# axiom_beta_interface_dummy_v0_13_r1_3.net
KiCad netlist of a schematic drawn in EAGLE
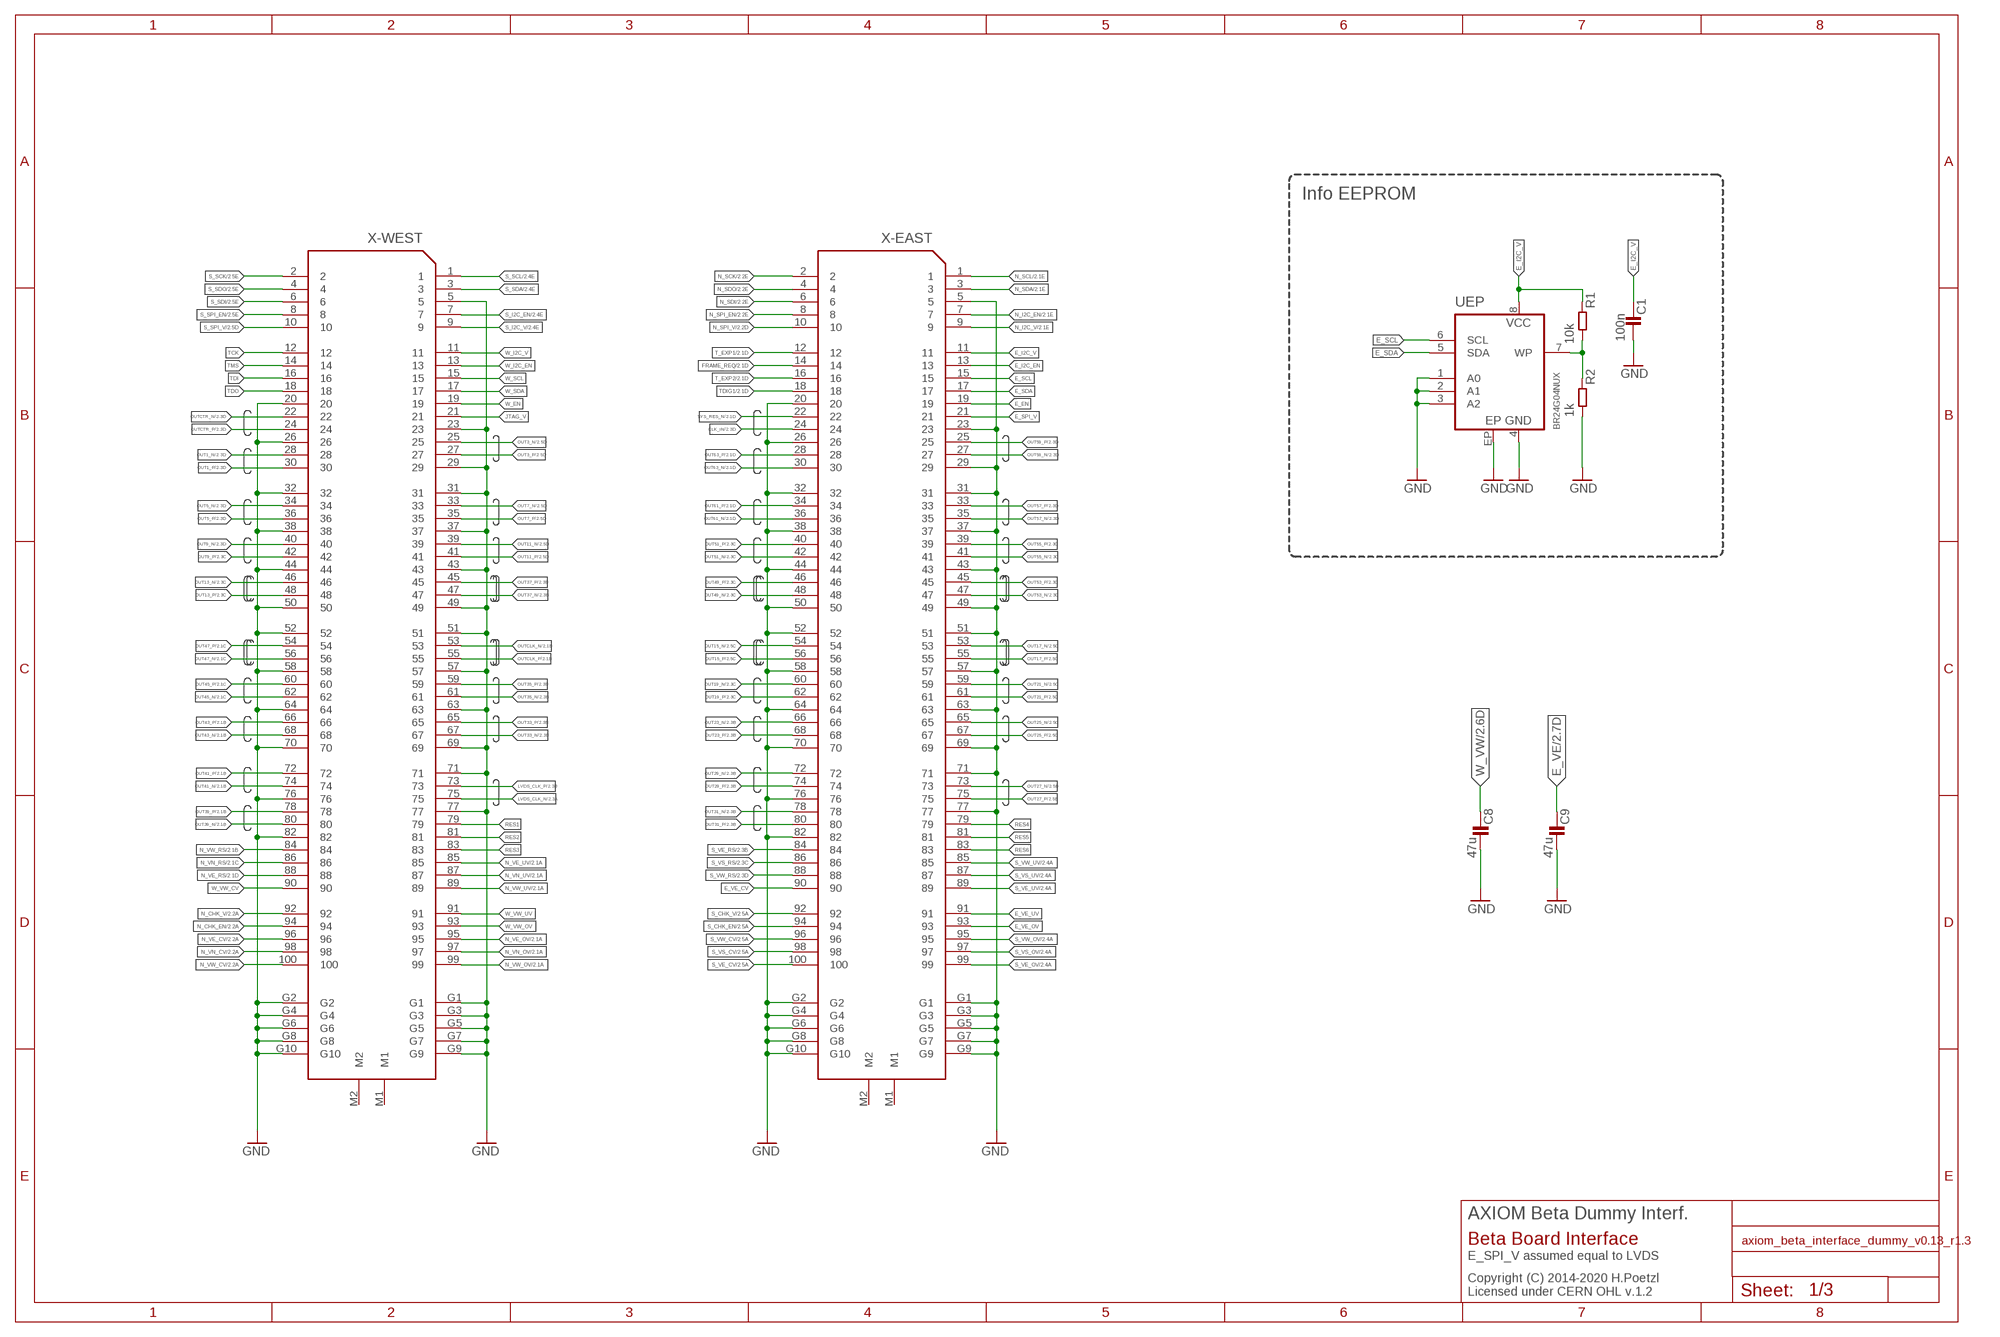
[diagram p0: schematic, sheet 1]
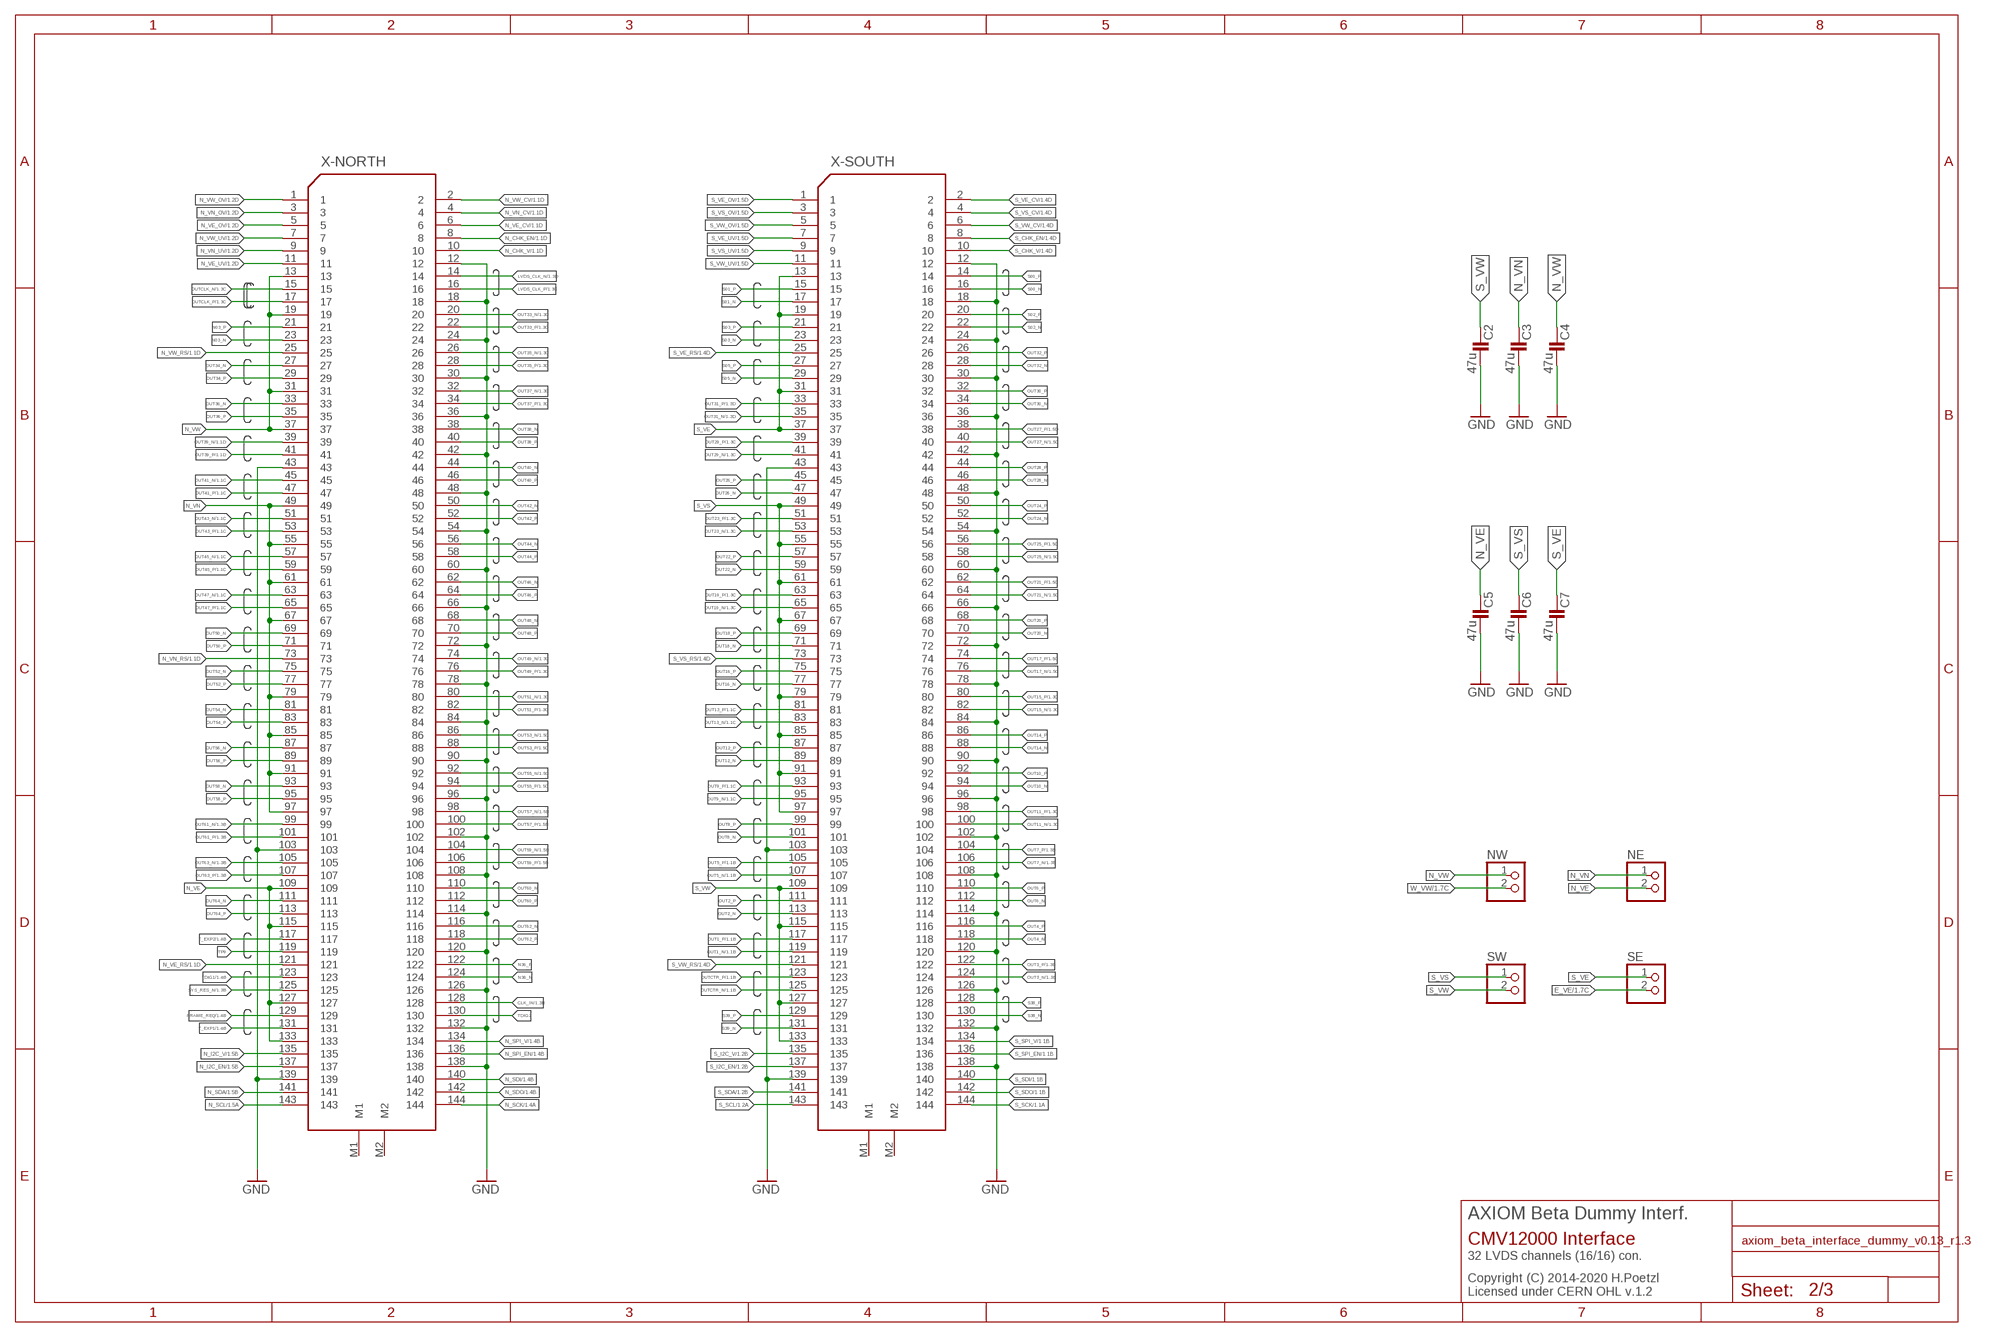
[diagram p1: schematic, sheet 2]
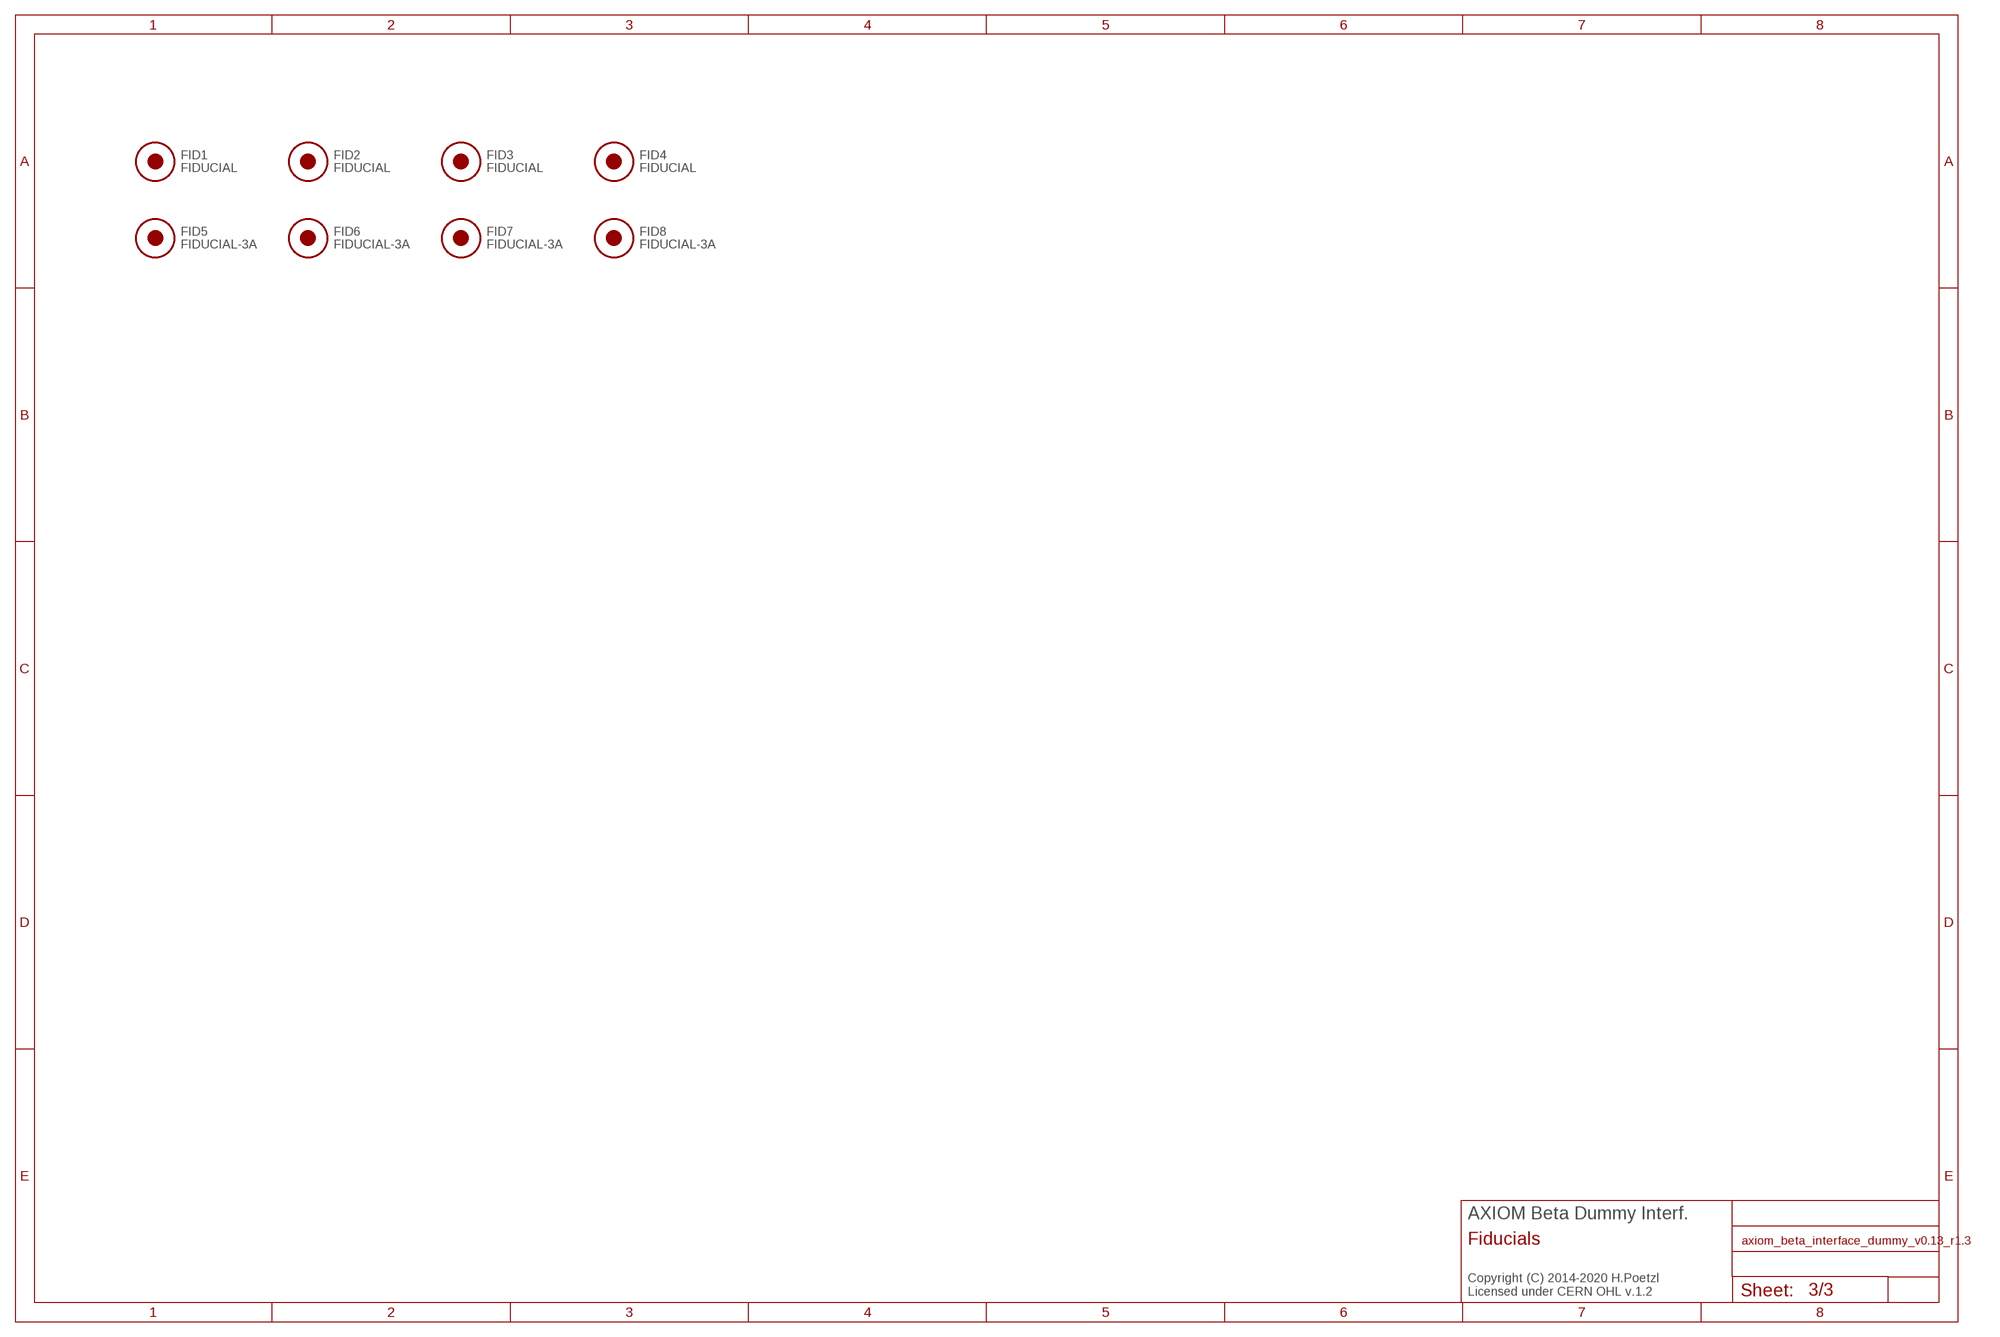
[diagram p2: schematic, sheet 3]

(export (version "E")
  (design (tool "Eeschema 10.0.6"))
  (components
    (comp (ref "C1")
      (value "100n")
      (footprint "eagle-import:0402-B")
      (libsource (lib "eagle-import") (part "C0402-B"))
    )
    (comp (ref "C8")
      (value "47u")
      (footprint "eagle-import:0805-B")
      (libsource (lib "eagle-import") (part "C0805-B"))
    )
    (comp (ref "C9")
      (value "47u")
      (footprint "eagle-import:0805-B")
      (libsource (lib "eagle-import") (part "C0805-B"))
    )
    (comp (ref "R1")
      (value "10k")
      (footprint "eagle-import:0402-B")
      (libsource (lib "eagle-import") (part "R0402-B"))
    )
    (comp (ref "R2")
      (value "1k")
      (footprint "eagle-import:0402-B")
      (libsource (lib "eagle-import") (part "R0402-B"))
    )
    (comp (ref "UEP")
      (value "BR24G04NUX")
      (footprint "eagle-import:DFN200X300X100-9N")
      (libsource (lib "eagle-import") (part "BR24G04NUX"))
    )
    (comp (ref "X-EAST")
      (value "FX10-100/10P")
      (footprint "eagle-import:FX10A-100P_10")
      (libsource (lib "eagle-import") (part "FX10-100/10P"))
    )
    (comp (ref "X-WEST")
      (value "FX10-100/10P")
      (footprint "eagle-import:FX10A-100P_10")
      (libsource (lib "eagle-import") (part "FX10-100/10P"))
    )
    (comp (ref "FID1")
      (value "FIDUCIAL")
      (footprint "eagle-import:FID_ARROW")
      (libsource (lib "eagle-import") (part "FIDUCIAL"))
    )
    (comp (ref "FID2")
      (value "FIDUCIAL")
      (footprint "eagle-import:FID_ARROW")
      (libsource (lib "eagle-import") (part "FIDUCIAL"))
    )
    (comp (ref "FID3")
      (value "FIDUCIAL")
      (footprint "eagle-import:FID_ARROW")
      (libsource (lib "eagle-import") (part "FIDUCIAL"))
    )
    (comp (ref "FID4")
      (value "FIDUCIAL")
      (footprint "eagle-import:FID_ARROW")
      (libsource (lib "eagle-import") (part "FIDUCIAL"))
    )
    (comp (ref "FID5")
      (value "FIDUCIAL-3A")
      (footprint "eagle-import:FID_3ARROW")
      (libsource (lib "eagle-import") (part "FIDUCIAL-3A"))
    )
    (comp (ref "FID6")
      (value "FIDUCIAL-3A")
      (footprint "eagle-import:FID_3ARROW")
      (libsource (lib "eagle-import") (part "FIDUCIAL-3A"))
    )
    (comp (ref "FID7")
      (value "FIDUCIAL-3A")
      (footprint "eagle-import:FID_3ARROW")
      (libsource (lib "eagle-import") (part "FIDUCIAL-3A"))
    )
    (comp (ref "FID8")
      (value "FIDUCIAL-3A")
      (footprint "eagle-import:FID_3ARROW")
      (libsource (lib "eagle-import") (part "FIDUCIAL-3A"))
    )
    (comp (ref "C2")
      (value "47u")
      (footprint "eagle-import:0805-B")
      (libsource (lib "eagle-import") (part "C0805-B"))
    )
    (comp (ref "C3")
      (value "47u")
      (footprint "eagle-import:0805-B")
      (libsource (lib "eagle-import") (part "C0805-B"))
    )
    (comp (ref "C4")
      (value "47u")
      (footprint "eagle-import:0805-B")
      (libsource (lib "eagle-import") (part "C0805-B"))
    )
    (comp (ref "C5")
      (value "47u")
      (footprint "eagle-import:0805-B")
      (libsource (lib "eagle-import") (part "C0805-B"))
    )
    (comp (ref "C6")
      (value "47u")
      (footprint "eagle-import:0805-B")
      (libsource (lib "eagle-import") (part "C0805-B"))
    )
    (comp (ref "C7")
      (value "47u")
      (footprint "eagle-import:0805-B")
      (libsource (lib "eagle-import") (part "C0805-B"))
    )
    (comp (ref "NE")
      (value "PINHD-1X02_2.54")
      (footprint "eagle-import:1X02")
      (libsource (lib "eagle-import") (part "PINHD-1X02_2.54"))
    )
    (comp (ref "NW")
      (value "PINHD-1X02_2.54")
      (footprint "eagle-import:1X02")
      (libsource (lib "eagle-import") (part "PINHD-1X02_2.54"))
    )
    (comp (ref "SE")
      (value "PINHD-1X02_2.54")
      (footprint "eagle-import:1X02")
      (libsource (lib "eagle-import") (part "PINHD-1X02_2.54"))
    )
    (comp (ref "SW")
      (value "PINHD-1X02_2.54")
      (footprint "eagle-import:1X02")
      (libsource (lib "eagle-import") (part "PINHD-1X02_2.54"))
    )
    (comp (ref "X-NORTH")
      (value "FX10-144S")
      (footprint "eagle-import:FX10A-144S")
      (libsource (lib "eagle-import") (part "FX10-144S"))
    )
    (comp (ref "X-SOUTH")
      (value "FX10-144S")
      (footprint "eagle-import:FX10A-144S")
      (libsource (lib "eagle-import") (part "FX10-144S"))
    )
  )
  (nets
    (net (code "1") (name "CLK_IN") (class "Default")
      (node (ref "X-EAST") (pin "24") (pinfunction "24_24") (pintype "bidirectional"))
      (node (ref "X-NORTH") (pin "128") (pinfunction "128_128") (pintype "bidirectional"))
    )
    (net (code "2") (name "E_EN") (class "Default")
      (node (ref "X-EAST") (pin "19") (pinfunction "19_19") (pintype "bidirectional"))
    )
    (net (code "3") (name "E_I2C_EN") (class "Default")
      (node (ref "X-EAST") (pin "13") (pinfunction "13_13") (pintype "bidirectional"))
    )
    (net (code "4") (name "E_I2C_V") (class "Default")
      (node (ref "C1") (pin "1") (pinfunction "1_1") (pintype "passive"))
      (node (ref "R1") (pin "1") (pinfunction "1_1") (pintype "passive"))
      (node (ref "UEP") (pin "8") (pinfunction "VCC_8") (pintype "power_in"))
      (node (ref "X-EAST") (pin "11") (pinfunction "11_11") (pintype "bidirectional"))
    )
    (net (code "5") (name "E_SCL") (class "Default")
      (node (ref "UEP") (pin "6") (pinfunction "SCL_6") (pintype "input"))
      (node (ref "X-EAST") (pin "15") (pinfunction "15_15") (pintype "bidirectional"))
    )
    (net (code "6") (name "E_SDA") (class "Default")
      (node (ref "UEP") (pin "5") (pinfunction "SDA_5") (pintype "bidirectional"))
      (node (ref "X-EAST") (pin "17") (pinfunction "17_17") (pintype "bidirectional"))
    )
    (net (code "7") (name "E_SPI_V") (class "Default")
      (node (ref "X-EAST") (pin "21") (pinfunction "21_21") (pintype "bidirectional"))
    )
    (net (code "8") (name "E_VE") (class "Default")
      (node (ref "C9") (pin "1") (pinfunction "1_1") (pintype "passive"))
      (node (ref "SE") (pin "2") (pinfunction "2_2") (pintype "passive"))
    )
    (net (code "9") (name "E_VE_CV") (class "Default")
      (node (ref "X-EAST") (pin "90") (pinfunction "90_90") (pintype "bidirectional"))
    )
    (net (code "10") (name "E_VE_OV") (class "Default")
      (node (ref "X-EAST") (pin "93") (pinfunction "93_93") (pintype "bidirectional"))
    )
    (net (code "11") (name "E_VE_UV") (class "Default")
      (node (ref "X-EAST") (pin "91") (pinfunction "91_91") (pintype "bidirectional"))
    )
    (net (code "12") (name "FRAME_REQ") (class "Default")
      (node (ref "X-EAST") (pin "14") (pinfunction "14_14") (pintype "bidirectional"))
      (node (ref "X-NORTH") (pin "129") (pinfunction "129_129") (pintype "bidirectional"))
    )
    (net (code "13") (name "GND") (class "Default")
      (node (ref "C1") (pin "2") (pinfunction "2_2") (pintype "passive"))
      (node (ref "C2") (pin "2") (pinfunction "2_2") (pintype "passive"))
      (node (ref "C3") (pin "2") (pinfunction "2_2") (pintype "passive"))
      (node (ref "C4") (pin "2") (pinfunction "2_2") (pintype "passive"))
      (node (ref "C5") (pin "2") (pinfunction "2_2") (pintype "passive"))
      (node (ref "C6") (pin "2") (pinfunction "2_2") (pintype "passive"))
      (node (ref "C7") (pin "2") (pinfunction "2_2") (pintype "passive"))
      (node (ref "C8") (pin "2") (pinfunction "2_2") (pintype "passive"))
      (node (ref "C9") (pin "2") (pinfunction "2_2") (pintype "passive"))
      (node (ref "R2") (pin "2") (pinfunction "2_2") (pintype "passive"))
      (node (ref "UEP") (pin "1") (pinfunction "A0_1") (pintype "input"))
      (node (ref "UEP") (pin "2") (pinfunction "A1_2") (pintype "input"))
      (node (ref "UEP") (pin "3") (pinfunction "A2_3") (pintype "input"))
      (node (ref "UEP") (pin "4") (pinfunction "GND_4") (pintype "passive"))
      (node (ref "UEP") (pin "EP") (pinfunction "EP_EP") (pintype "passive"))
      (node (ref "X-EAST") (pin "20") (pinfunction "20_20") (pintype "bidirectional"))
      (node (ref "X-EAST") (pin "23") (pinfunction "23_23") (pintype "bidirectional"))
      (node (ref "X-EAST") (pin "26") (pinfunction "26_26") (pintype "bidirectional"))
      (node (ref "X-EAST") (pin "29") (pinfunction "29_29") (pintype "bidirectional"))
      (node (ref "X-EAST") (pin "31") (pinfunction "31_31") (pintype "bidirectional"))
      (node (ref "X-EAST") (pin "32") (pinfunction "32_32") (pintype "bidirectional"))
      (node (ref "X-EAST") (pin "37") (pinfunction "37_37") (pintype "bidirectional"))
      (node (ref "X-EAST") (pin "38") (pinfunction "38_38") (pintype "bidirectional"))
      (node (ref "X-EAST") (pin "43") (pinfunction "43_43") (pintype "bidirectional"))
      (node (ref "X-EAST") (pin "44") (pinfunction "44_44") (pintype "bidirectional"))
      (node (ref "X-EAST") (pin "49") (pinfunction "49_49") (pintype "bidirectional"))
      (node (ref "X-EAST") (pin "5") (pinfunction "5_5") (pintype "bidirectional"))
      (node (ref "X-EAST") (pin "50") (pinfunction "50_50") (pintype "bidirectional"))
      (node (ref "X-EAST") (pin "51") (pinfunction "51_51") (pintype "bidirectional"))
      (node (ref "X-EAST") (pin "52") (pinfunction "52_52") (pintype "bidirectional"))
      (node (ref "X-EAST") (pin "57") (pinfunction "57_57") (pintype "bidirectional"))
      (node (ref "X-EAST") (pin "58") (pinfunction "58_58") (pintype "bidirectional"))
      (node (ref "X-EAST") (pin "63") (pinfunction "63_63") (pintype "bidirectional"))
      (node (ref "X-EAST") (pin "64") (pinfunction "64_64") (pintype "bidirectional"))
      (node (ref "X-EAST") (pin "69") (pinfunction "69_69") (pintype "bidirectional"))
      (node (ref "X-EAST") (pin "70") (pinfunction "70_70") (pintype "bidirectional"))
      (node (ref "X-EAST") (pin "71") (pinfunction "71_71") (pintype "bidirectional"))
      (node (ref "X-EAST") (pin "76") (pinfunction "76_76") (pintype "bidirectional"))
      (node (ref "X-EAST") (pin "77") (pinfunction "77_77") (pintype "bidirectional"))
      (node (ref "X-EAST") (pin "82") (pinfunction "82_82") (pintype "bidirectional"))
      (node (ref "X-EAST") (pin "G1") (pinfunction "G1_G1") (pintype "bidirectional"))
      (node (ref "X-EAST") (pin "G10") (pinfunction "G10_G10") (pintype "bidirectional"))
      (node (ref "X-EAST") (pin "G2") (pinfunction "G2_G2") (pintype "bidirectional"))
      (node (ref "X-EAST") (pin "G3") (pinfunction "G3_G3") (pintype "bidirectional"))
      (node (ref "X-EAST") (pin "G4") (pinfunction "G4_G4") (pintype "bidirectional"))
      (node (ref "X-EAST") (pin "G5") (pinfunction "G5_G5") (pintype "bidirectional"))
      (node (ref "X-EAST") (pin "G6") (pinfunction "G6_G6") (pintype "bidirectional"))
      (node (ref "X-EAST") (pin "G7") (pinfunction "G7_G7") (pintype "bidirectional"))
      (node (ref "X-EAST") (pin "G8") (pinfunction "G8_G8") (pintype "bidirectional"))
      (node (ref "X-EAST") (pin "G9") (pinfunction "G9_G9") (pintype "bidirectional"))
      (node (ref "X-NORTH") (pin "102") (pinfunction "102_102") (pintype "bidirectional"))
      (node (ref "X-NORTH") (pin "103") (pinfunction "103_103") (pintype "bidirectional"))
      (node (ref "X-NORTH") (pin "108") (pinfunction "108_108") (pintype "bidirectional"))
      (node (ref "X-NORTH") (pin "114") (pinfunction "114_114") (pintype "bidirectional"))
      (node (ref "X-NORTH") (pin "12") (pinfunction "12_12") (pintype "bidirectional"))
      (node (ref "X-NORTH") (pin "120") (pinfunction "120_120") (pintype "bidirectional"))
      (node (ref "X-NORTH") (pin "126") (pinfunction "126_126") (pintype "bidirectional"))
      (node (ref "X-NORTH") (pin "132") (pinfunction "132_132") (pintype "bidirectional"))
      (node (ref "X-NORTH") (pin "138") (pinfunction "138_138") (pintype "bidirectional"))
      (node (ref "X-NORTH") (pin "139") (pinfunction "139_139") (pintype "bidirectional"))
      (node (ref "X-NORTH") (pin "18") (pinfunction "18_18") (pintype "bidirectional"))
      (node (ref "X-NORTH") (pin "24") (pinfunction "24_24") (pintype "bidirectional"))
      (node (ref "X-NORTH") (pin "30") (pinfunction "30_30") (pintype "bidirectional"))
      (node (ref "X-NORTH") (pin "36") (pinfunction "36_36") (pintype "bidirectional"))
      (node (ref "X-NORTH") (pin "42") (pinfunction "42_42") (pintype "bidirectional"))
      (node (ref "X-NORTH") (pin "43") (pinfunction "43_43") (pintype "bidirectional"))
      (node (ref "X-NORTH") (pin "48") (pinfunction "48_48") (pintype "bidirectional"))
      (node (ref "X-NORTH") (pin "54") (pinfunction "54_54") (pintype "bidirectional"))
      (node (ref "X-NORTH") (pin "60") (pinfunction "60_60") (pintype "bidirectional"))
      (node (ref "X-NORTH") (pin "66") (pinfunction "66_66") (pintype "bidirectional"))
      (node (ref "X-NORTH") (pin "72") (pinfunction "72_72") (pintype "bidirectional"))
      (node (ref "X-NORTH") (pin "78") (pinfunction "78_78") (pintype "bidirectional"))
      (node (ref "X-NORTH") (pin "84") (pinfunction "84_84") (pintype "bidirectional"))
      (node (ref "X-NORTH") (pin "90") (pinfunction "90_90") (pintype "bidirectional"))
      (node (ref "X-NORTH") (pin "96") (pinfunction "96_96") (pintype "bidirectional"))
      (node (ref "X-SOUTH") (pin "102") (pinfunction "102_102") (pintype "bidirectional"))
      (node (ref "X-SOUTH") (pin "103") (pinfunction "103_103") (pintype "bidirectional"))
      (node (ref "X-SOUTH") (pin "108") (pinfunction "108_108") (pintype "bidirectional"))
      (node (ref "X-SOUTH") (pin "114") (pinfunction "114_114") (pintype "bidirectional"))
      (node (ref "X-SOUTH") (pin "12") (pinfunction "12_12") (pintype "bidirectional"))
      (node (ref "X-SOUTH") (pin "120") (pinfunction "120_120") (pintype "bidirectional"))
      (node (ref "X-SOUTH") (pin "126") (pinfunction "126_126") (pintype "bidirectional"))
      (node (ref "X-SOUTH") (pin "132") (pinfunction "132_132") (pintype "bidirectional"))
      (node (ref "X-SOUTH") (pin "138") (pinfunction "138_138") (pintype "bidirectional"))
      (node (ref "X-SOUTH") (pin "139") (pinfunction "139_139") (pintype "bidirectional"))
      (node (ref "X-SOUTH") (pin "18") (pinfunction "18_18") (pintype "bidirectional"))
      (node (ref "X-SOUTH") (pin "24") (pinfunction "24_24") (pintype "bidirectional"))
      (node (ref "X-SOUTH") (pin "30") (pinfunction "30_30") (pintype "bidirectional"))
      (node (ref "X-SOUTH") (pin "36") (pinfunction "36_36") (pintype "bidirectional"))
      (node (ref "X-SOUTH") (pin "42") (pinfunction "42_42") (pintype "bidirectional"))
      (node (ref "X-SOUTH") (pin "43") (pinfunction "43_43") (pintype "bidirectional"))
      (node (ref "X-SOUTH") (pin "48") (pinfunction "48_48") (pintype "bidirectional"))
      (node (ref "X-SOUTH") (pin "54") (pinfunction "54_54") (pintype "bidirectional"))
      (node (ref "X-SOUTH") (pin "60") (pinfunction "60_60") (pintype "bidirectional"))
      (node (ref "X-SOUTH") (pin "66") (pinfunction "66_66") (pintype "bidirectional"))
      (node (ref "X-SOUTH") (pin "72") (pinfunction "72_72") (pintype "bidirectional"))
      (node (ref "X-SOUTH") (pin "78") (pinfunction "78_78") (pintype "bidirectional"))
      (node (ref "X-SOUTH") (pin "84") (pinfunction "84_84") (pintype "bidirectional"))
      (node (ref "X-SOUTH") (pin "90") (pinfunction "90_90") (pintype "bidirectional"))
      (node (ref "X-SOUTH") (pin "96") (pinfunction "96_96") (pintype "bidirectional"))
      (node (ref "X-WEST") (pin "20") (pinfunction "20_20") (pintype "bidirectional"))
      (node (ref "X-WEST") (pin "23") (pinfunction "23_23") (pintype "bidirectional"))
      (node (ref "X-WEST") (pin "26") (pinfunction "26_26") (pintype "bidirectional"))
      (node (ref "X-WEST") (pin "29") (pinfunction "29_29") (pintype "bidirectional"))
      (node (ref "X-WEST") (pin "31") (pinfunction "31_31") (pintype "bidirectional"))
      (node (ref "X-WEST") (pin "32") (pinfunction "32_32") (pintype "bidirectional"))
      (node (ref "X-WEST") (pin "37") (pinfunction "37_37") (pintype "bidirectional"))
      (node (ref "X-WEST") (pin "38") (pinfunction "38_38") (pintype "bidirectional"))
      (node (ref "X-WEST") (pin "43") (pinfunction "43_43") (pintype "bidirectional"))
      (node (ref "X-WEST") (pin "44") (pinfunction "44_44") (pintype "bidirectional"))
      (node (ref "X-WEST") (pin "49") (pinfunction "49_49") (pintype "bidirectional"))
      (node (ref "X-WEST") (pin "5") (pinfunction "5_5") (pintype "bidirectional"))
      (node (ref "X-WEST") (pin "50") (pinfunction "50_50") (pintype "bidirectional"))
      (node (ref "X-WEST") (pin "51") (pinfunction "51_51") (pintype "bidirectional"))
      (node (ref "X-WEST") (pin "52") (pinfunction "52_52") (pintype "bidirectional"))
      (node (ref "X-WEST") (pin "57") (pinfunction "57_57") (pintype "bidirectional"))
      (node (ref "X-WEST") (pin "58") (pinfunction "58_58") (pintype "bidirectional"))
      (node (ref "X-WEST") (pin "63") (pinfunction "63_63") (pintype "bidirectional"))
      (node (ref "X-WEST") (pin "64") (pinfunction "64_64") (pintype "bidirectional"))
      (node (ref "X-WEST") (pin "69") (pinfunction "69_69") (pintype "bidirectional"))
      (node (ref "X-WEST") (pin "70") (pinfunction "70_70") (pintype "bidirectional"))
      (node (ref "X-WEST") (pin "71") (pinfunction "71_71") (pintype "bidirectional"))
      (node (ref "X-WEST") (pin "76") (pinfunction "76_76") (pintype "bidirectional"))
      (node (ref "X-WEST") (pin "77") (pinfunction "77_77") (pintype "bidirectional"))
      (node (ref "X-WEST") (pin "82") (pinfunction "82_82") (pintype "bidirectional"))
      (node (ref "X-WEST") (pin "G1") (pinfunction "G1_G1") (pintype "bidirectional"))
      (node (ref "X-WEST") (pin "G10") (pinfunction "G10_G10") (pintype "bidirectional"))
      (node (ref "X-WEST") (pin "G2") (pinfunction "G2_G2") (pintype "bidirectional"))
      (node (ref "X-WEST") (pin "G3") (pinfunction "G3_G3") (pintype "bidirectional"))
      (node (ref "X-WEST") (pin "G4") (pinfunction "G4_G4") (pintype "bidirectional"))
      (node (ref "X-WEST") (pin "G5") (pinfunction "G5_G5") (pintype "bidirectional"))
      (node (ref "X-WEST") (pin "G6") (pinfunction "G6_G6") (pintype "bidirectional"))
      (node (ref "X-WEST") (pin "G7") (pinfunction "G7_G7") (pintype "bidirectional"))
      (node (ref "X-WEST") (pin "G8") (pinfunction "G8_G8") (pintype "bidirectional"))
      (node (ref "X-WEST") (pin "G9") (pinfunction "G9_G9") (pintype "bidirectional"))
    )
    (net (code "14") (name "JTAG_V") (class "Default")
      (node (ref "X-WEST") (pin "21") (pinfunction "21_21") (pintype "bidirectional"))
    )
    (net (code "15") (name "LVDS_CLK_N") (class "Default")
      (node (ref "X-NORTH") (pin "14") (pinfunction "14_14") (pintype "bidirectional"))
      (node (ref "X-WEST") (pin "75") (pinfunction "75_75") (pintype "bidirectional"))
    )
    (net (code "16") (name "LVDS_CLK_P") (class "Default")
      (node (ref "X-NORTH") (pin "16") (pinfunction "16_16") (pintype "bidirectional"))
      (node (ref "X-WEST") (pin "73") (pinfunction "73_73") (pintype "bidirectional"))
    )
    (net (code "17") (name "N03_N") (class "Default")
      (node (ref "X-NORTH") (pin "23") (pinfunction "23_23") (pintype "bidirectional"))
    )
    (net (code "18") (name "N03_P") (class "Default")
      (node (ref "X-NORTH") (pin "21") (pinfunction "21_21") (pintype "bidirectional"))
    )
    (net (code "19") (name "N36_N") (class "Default")
      (node (ref "X-NORTH") (pin "124") (pinfunction "124_124") (pintype "bidirectional"))
    )
    (net (code "20") (name "N36_P") (class "Default")
      (node (ref "X-NORTH") (pin "122") (pinfunction "122_122") (pintype "bidirectional"))
    )
    (net (code "21") (name "N_CHK_EN") (class "Default")
      (node (ref "X-NORTH") (pin "8") (pinfunction "8_8") (pintype "bidirectional"))
      (node (ref "X-WEST") (pin "94") (pinfunction "94_94") (pintype "bidirectional"))
    )
    (net (code "22") (name "N_CHK_V") (class "Default")
      (node (ref "X-NORTH") (pin "10") (pinfunction "10_10") (pintype "bidirectional"))
      (node (ref "X-WEST") (pin "92") (pinfunction "92_92") (pintype "bidirectional"))
    )
    (net (code "23") (name "N_I2C_EN") (class "Default")
      (node (ref "X-EAST") (pin "7") (pinfunction "7_7") (pintype "bidirectional"))
      (node (ref "X-NORTH") (pin "137") (pinfunction "137_137") (pintype "bidirectional"))
    )
    (net (code "24") (name "N_I2C_V") (class "Default")
      (node (ref "X-EAST") (pin "9") (pinfunction "9_9") (pintype "bidirectional"))
      (node (ref "X-NORTH") (pin "135") (pinfunction "135_135") (pintype "bidirectional"))
    )
    (net (code "25") (name "N_SCK") (class "Default")
      (node (ref "X-EAST") (pin "2") (pinfunction "2_2") (pintype "bidirectional"))
      (node (ref "X-NORTH") (pin "144") (pinfunction "144_144") (pintype "bidirectional"))
    )
    (net (code "26") (name "N_SCL") (class "Default")
      (node (ref "X-EAST") (pin "1") (pinfunction "1_1") (pintype "bidirectional"))
      (node (ref "X-NORTH") (pin "143") (pinfunction "143_143") (pintype "bidirectional"))
    )
    (net (code "27") (name "N_SDA") (class "Default")
      (node (ref "X-EAST") (pin "3") (pinfunction "3_3") (pintype "bidirectional"))
      (node (ref "X-NORTH") (pin "141") (pinfunction "141_141") (pintype "bidirectional"))
    )
    (net (code "28") (name "N_SDI") (class "Default")
      (node (ref "X-EAST") (pin "6") (pinfunction "6_6") (pintype "bidirectional"))
      (node (ref "X-NORTH") (pin "140") (pinfunction "140_140") (pintype "bidirectional"))
    )
    (net (code "29") (name "N_SDO") (class "Default")
      (node (ref "X-EAST") (pin "4") (pinfunction "4_4") (pintype "bidirectional"))
      (node (ref "X-NORTH") (pin "142") (pinfunction "142_142") (pintype "bidirectional"))
    )
    (net (code "30") (name "N_SPI_EN") (class "Default")
      (node (ref "X-EAST") (pin "8") (pinfunction "8_8") (pintype "bidirectional"))
      (node (ref "X-NORTH") (pin "136") (pinfunction "136_136") (pintype "bidirectional"))
    )
    (net (code "31") (name "N_SPI_V") (class "Default")
      (node (ref "X-EAST") (pin "10") (pinfunction "10_10") (pintype "bidirectional"))
      (node (ref "X-NORTH") (pin "134") (pinfunction "134_134") (pintype "bidirectional"))
    )
    (net (code "32") (name "N_VE") (class "Default")
      (node (ref "C5") (pin "1") (pinfunction "1_1") (pintype "passive"))
      (node (ref "NE") (pin "2") (pinfunction "2_2") (pintype "passive"))
      (node (ref "X-NORTH") (pin "109") (pinfunction "109_109") (pintype "bidirectional"))
      (node (ref "X-NORTH") (pin "115") (pinfunction "115_115") (pintype "bidirectional"))
      (node (ref "X-NORTH") (pin "127") (pinfunction "127_127") (pintype "bidirectional"))
      (node (ref "X-NORTH") (pin "133") (pinfunction "133_133") (pintype "bidirectional"))
    )
    (net (code "33") (name "N_VE_CV") (class "Default")
      (node (ref "X-NORTH") (pin "6") (pinfunction "6_6") (pintype "bidirectional"))
      (node (ref "X-WEST") (pin "96") (pinfunction "96_96") (pintype "bidirectional"))
    )
    (net (code "34") (name "N_VE_OV") (class "Default")
      (node (ref "X-NORTH") (pin "5") (pinfunction "5_5") (pintype "bidirectional"))
      (node (ref "X-WEST") (pin "95") (pinfunction "95_95") (pintype "bidirectional"))
    )
    (net (code "35") (name "N_VE_RS") (class "Default")
      (node (ref "X-NORTH") (pin "121") (pinfunction "121_121") (pintype "bidirectional"))
      (node (ref "X-WEST") (pin "88") (pinfunction "88_88") (pintype "bidirectional"))
    )
    (net (code "36") (name "N_VE_UV") (class "Default")
      (node (ref "X-NORTH") (pin "11") (pinfunction "11_11") (pintype "bidirectional"))
      (node (ref "X-WEST") (pin "85") (pinfunction "85_85") (pintype "bidirectional"))
    )
    (net (code "37") (name "N_VN") (class "Default")
      (node (ref "C3") (pin "1") (pinfunction "1_1") (pintype "passive"))
      (node (ref "NE") (pin "1") (pinfunction "1_1") (pintype "passive"))
      (node (ref "X-NORTH") (pin "49") (pinfunction "49_49") (pintype "bidirectional"))
      (node (ref "X-NORTH") (pin "55") (pinfunction "55_55") (pintype "bidirectional"))
      (node (ref "X-NORTH") (pin "61") (pinfunction "61_61") (pintype "bidirectional"))
      (node (ref "X-NORTH") (pin "67") (pinfunction "67_67") (pintype "bidirectional"))
      (node (ref "X-NORTH") (pin "79") (pinfunction "79_79") (pintype "bidirectional"))
      (node (ref "X-NORTH") (pin "85") (pinfunction "85_85") (pintype "bidirectional"))
      (node (ref "X-NORTH") (pin "91") (pinfunction "91_91") (pintype "bidirectional"))
      (node (ref "X-NORTH") (pin "97") (pinfunction "97_97") (pintype "bidirectional"))
    )
    (net (code "38") (name "N_VN_CV") (class "Default")
      (node (ref "X-NORTH") (pin "4") (pinfunction "4_4") (pintype "bidirectional"))
      (node (ref "X-WEST") (pin "98") (pinfunction "98_98") (pintype "bidirectional"))
    )
    (net (code "39") (name "N_VN_OV") (class "Default")
      (node (ref "X-NORTH") (pin "3") (pinfunction "3_3") (pintype "bidirectional"))
      (node (ref "X-WEST") (pin "97") (pinfunction "97_97") (pintype "bidirectional"))
    )
    (net (code "40") (name "N_VN_RS") (class "Default")
      (node (ref "X-NORTH") (pin "73") (pinfunction "73_73") (pintype "bidirectional"))
      (node (ref "X-WEST") (pin "86") (pinfunction "86_86") (pintype "bidirectional"))
    )
    (net (code "41") (name "N_VN_UV") (class "Default")
      (node (ref "X-NORTH") (pin "9") (pinfunction "9_9") (pintype "bidirectional"))
      (node (ref "X-WEST") (pin "87") (pinfunction "87_87") (pintype "bidirectional"))
    )
    (net (code "42") (name "N_VW") (class "Default")
      (node (ref "C4") (pin "1") (pinfunction "1_1") (pintype "passive"))
      (node (ref "NW") (pin "1") (pinfunction "1_1") (pintype "passive"))
      (node (ref "X-NORTH") (pin "13") (pinfunction "13_13") (pintype "bidirectional"))
      (node (ref "X-NORTH") (pin "19") (pinfunction "19_19") (pintype "bidirectional"))
      (node (ref "X-NORTH") (pin "31") (pinfunction "31_31") (pintype "bidirectional"))
      (node (ref "X-NORTH") (pin "37") (pinfunction "37_37") (pintype "bidirectional"))
    )
    (net (code "43") (name "N_VW_CV") (class "Default")
      (node (ref "X-NORTH") (pin "2") (pinfunction "2_2") (pintype "bidirectional"))
      (node (ref "X-WEST") (pin "100") (pinfunction "100_100") (pintype "bidirectional"))
    )
    (net (code "44") (name "N_VW_OV") (class "Default")
      (node (ref "X-NORTH") (pin "1") (pinfunction "1_1") (pintype "bidirectional"))
      (node (ref "X-WEST") (pin "99") (pinfunction "99_99") (pintype "bidirectional"))
    )
    (net (code "45") (name "N_VW_RS") (class "Default")
      (node (ref "X-NORTH") (pin "25") (pinfunction "25_25") (pintype "bidirectional"))
      (node (ref "X-WEST") (pin "84") (pinfunction "84_84") (pintype "bidirectional"))
    )
    (net (code "46") (name "N_VW_UV") (class "Default")
      (node (ref "X-NORTH") (pin "7") (pinfunction "7_7") (pintype "bidirectional"))
      (node (ref "X-WEST") (pin "89") (pinfunction "89_89") (pintype "bidirectional"))
    )
    (net (code "47") (name "Net-(UEP-WP)") (class "Default")
      (node (ref "R1") (pin "2") (pinfunction "2_2") (pintype "passive"))
      (node (ref "R2") (pin "1") (pinfunction "1_1") (pintype "passive"))
      (node (ref "UEP") (pin "7") (pinfunction "WP_7") (pintype "input"))
    )
    (net (code "48") (name "OUT1_N") (class "Default")
      (node (ref "X-SOUTH") (pin "119") (pinfunction "119_119") (pintype "bidirectional"))
      (node (ref "X-WEST") (pin "28") (pinfunction "28_28") (pintype "bidirectional"))
    )
    (net (code "49") (name "OUT1_P") (class "Default")
      (node (ref "X-SOUTH") (pin "117") (pinfunction "117_117") (pintype "bidirectional"))
      (node (ref "X-WEST") (pin "30") (pinfunction "30_30") (pintype "bidirectional"))
    )
    (net (code "50") (name "OUT2_N") (class "Default")
      (node (ref "X-SOUTH") (pin "113") (pinfunction "113_113") (pintype "bidirectional"))
    )
    (net (code "51") (name "OUT2_P") (class "Default")
      (node (ref "X-SOUTH") (pin "111") (pinfunction "111_111") (pintype "bidirectional"))
    )
    (net (code "52") (name "OUT3_N") (class "Default")
      (node (ref "X-SOUTH") (pin "124") (pinfunction "124_124") (pintype "bidirectional"))
      (node (ref "X-WEST") (pin "25") (pinfunction "25_25") (pintype "bidirectional"))
    )
    (net (code "53") (name "OUT3_P") (class "Default")
      (node (ref "X-SOUTH") (pin "122") (pinfunction "122_122") (pintype "bidirectional"))
      (node (ref "X-WEST") (pin "27") (pinfunction "27_27") (pintype "bidirectional"))
    )
    (net (code "54") (name "OUT4_N") (class "Default")
      (node (ref "X-SOUTH") (pin "118") (pinfunction "118_118") (pintype "bidirectional"))
    )
    (net (code "55") (name "OUT4_P") (class "Default")
      (node (ref "X-SOUTH") (pin "116") (pinfunction "116_116") (pintype "bidirectional"))
    )
    (net (code "56") (name "OUT5_N") (class "Default")
      (node (ref "X-SOUTH") (pin "107") (pinfunction "107_107") (pintype "bidirectional"))
      (node (ref "X-WEST") (pin "34") (pinfunction "34_34") (pintype "bidirectional"))
    )
    (net (code "57") (name "OUT5_P") (class "Default")
      (node (ref "X-SOUTH") (pin "105") (pinfunction "105_105") (pintype "bidirectional"))
      (node (ref "X-WEST") (pin "36") (pinfunction "36_36") (pintype "bidirectional"))
    )
    (net (code "58") (name "OUT6_N") (class "Default")
      (node (ref "X-SOUTH") (pin "112") (pinfunction "112_112") (pintype "bidirectional"))
    )
    (net (code "59") (name "OUT6_P") (class "Default")
      (node (ref "X-SOUTH") (pin "110") (pinfunction "110_110") (pintype "bidirectional"))
    )
    (net (code "60") (name "OUT7_N") (class "Default")
      (node (ref "X-SOUTH") (pin "106") (pinfunction "106_106") (pintype "bidirectional"))
      (node (ref "X-WEST") (pin "33") (pinfunction "33_33") (pintype "bidirectional"))
    )
    (net (code "61") (name "OUT7_P") (class "Default")
      (node (ref "X-SOUTH") (pin "104") (pinfunction "104_104") (pintype "bidirectional"))
      (node (ref "X-WEST") (pin "35") (pinfunction "35_35") (pintype "bidirectional"))
    )
    (net (code "62") (name "OUT8_N") (class "Default")
      (node (ref "X-SOUTH") (pin "101") (pinfunction "101_101") (pintype "bidirectional"))
    )
    (net (code "63") (name "OUT8_P") (class "Default")
      (node (ref "X-SOUTH") (pin "99") (pinfunction "99_99") (pintype "bidirectional"))
    )
    (net (code "64") (name "OUT9_N") (class "Default")
      (node (ref "X-SOUTH") (pin "95") (pinfunction "95_95") (pintype "bidirectional"))
      (node (ref "X-WEST") (pin "40") (pinfunction "40_40") (pintype "bidirectional"))
    )
    (net (code "65") (name "OUT9_P") (class "Default")
      (node (ref "X-SOUTH") (pin "93") (pinfunction "93_93") (pintype "bidirectional"))
      (node (ref "X-WEST") (pin "42") (pinfunction "42_42") (pintype "bidirectional"))
    )
    (net (code "66") (name "OUT10_N") (class "Default")
      (node (ref "X-SOUTH") (pin "94") (pinfunction "94_94") (pintype "bidirectional"))
    )
    (net (code "67") (name "OUT10_P") (class "Default")
      (node (ref "X-SOUTH") (pin "92") (pinfunction "92_92") (pintype "bidirectional"))
    )
    (net (code "68") (name "OUT11_N") (class "Default")
      (node (ref "X-SOUTH") (pin "100") (pinfunction "100_100") (pintype "bidirectional"))
      (node (ref "X-WEST") (pin "39") (pinfunction "39_39") (pintype "bidirectional"))
    )
    (net (code "69") (name "OUT11_P") (class "Default")
      (node (ref "X-SOUTH") (pin "98") (pinfunction "98_98") (pintype "bidirectional"))
      (node (ref "X-WEST") (pin "41") (pinfunction "41_41") (pintype "bidirectional"))
    )
    (net (code "70") (name "OUT12_N") (class "Default")
      (node (ref "X-SOUTH") (pin "89") (pinfunction "89_89") (pintype "bidirectional"))
    )
    (net (code "71") (name "OUT12_P") (class "Default")
      (node (ref "X-SOUTH") (pin "87") (pinfunction "87_87") (pintype "bidirectional"))
    )
    (net (code "72") (name "OUT13_N") (class "Default")
      (node (ref "X-SOUTH") (pin "83") (pinfunction "83_83") (pintype "bidirectional"))
      (node (ref "X-WEST") (pin "46") (pinfunction "46_46") (pintype "bidirectional"))
    )
    (net (code "73") (name "OUT13_P") (class "Default")
      (node (ref "X-SOUTH") (pin "81") (pinfunction "81_81") (pintype "bidirectional"))
      (node (ref "X-WEST") (pin "48") (pinfunction "48_48") (pintype "bidirectional"))
    )
    (net (code "74") (name "OUT14_N") (class "Default")
      (node (ref "X-SOUTH") (pin "88") (pinfunction "88_88") (pintype "bidirectional"))
    )
    (net (code "75") (name "OUT14_P") (class "Default")
      (node (ref "X-SOUTH") (pin "86") (pinfunction "86_86") (pintype "bidirectional"))
    )
    (net (code "76") (name "OUT15_N") (class "Default")
      (node (ref "X-EAST") (pin "54") (pinfunction "54_54") (pintype "bidirectional"))
      (node (ref "X-SOUTH") (pin "82") (pinfunction "82_82") (pintype "bidirectional"))
    )
    (net (code "77") (name "OUT15_P") (class "Default")
      (node (ref "X-EAST") (pin "56") (pinfunction "56_56") (pintype "bidirectional"))
      (node (ref "X-SOUTH") (pin "80") (pinfunction "80_80") (pintype "bidirectional"))
    )
    (net (code "78") (name "OUT16_N") (class "Default")
      (node (ref "X-SOUTH") (pin "77") (pinfunction "77_77") (pintype "bidirectional"))
    )
    (net (code "79") (name "OUT16_P") (class "Default")
      (node (ref "X-SOUTH") (pin "75") (pinfunction "75_75") (pintype "bidirectional"))
    )
    (net (code "80") (name "OUT17_N") (class "Default")
      (node (ref "X-EAST") (pin "53") (pinfunction "53_53") (pintype "bidirectional"))
      (node (ref "X-SOUTH") (pin "76") (pinfunction "76_76") (pintype "bidirectional"))
    )
    (net (code "81") (name "OUT17_P") (class "Default")
      (node (ref "X-EAST") (pin "55") (pinfunction "55_55") (pintype "bidirectional"))
      (node (ref "X-SOUTH") (pin "74") (pinfunction "74_74") (pintype "bidirectional"))
    )
    (net (code "82") (name "OUT18_N") (class "Default")
      (node (ref "X-SOUTH") (pin "71") (pinfunction "71_71") (pintype "bidirectional"))
    )
    (net (code "83") (name "OUT18_P") (class "Default")
      (node (ref "X-SOUTH") (pin "69") (pinfunction "69_69") (pintype "bidirectional"))
    )
    (net (code "84") (name "OUT19_N") (class "Default")
      (node (ref "X-EAST") (pin "60") (pinfunction "60_60") (pintype "bidirectional"))
      (node (ref "X-SOUTH") (pin "65") (pinfunction "65_65") (pintype "bidirectional"))
    )
    (net (code "85") (name "OUT19_P") (class "Default")
      (node (ref "X-EAST") (pin "62") (pinfunction "62_62") (pintype "bidirectional"))
      (node (ref "X-SOUTH") (pin "63") (pinfunction "63_63") (pintype "bidirectional"))
    )
    (net (code "86") (name "OUT20_N") (class "Default")
      (node (ref "X-SOUTH") (pin "70") (pinfunction "70_70") (pintype "bidirectional"))
    )
    (net (code "87") (name "OUT20_P") (class "Default")
      (node (ref "X-SOUTH") (pin "68") (pinfunction "68_68") (pintype "bidirectional"))
    )
    (net (code "88") (name "OUT21_N") (class "Default")
      (node (ref "X-EAST") (pin "59") (pinfunction "59_59") (pintype "bidirectional"))
      (node (ref "X-SOUTH") (pin "64") (pinfunction "64_64") (pintype "bidirectional"))
    )
    (net (code "89") (name "OUT21_P") (class "Default")
      (node (ref "X-EAST") (pin "61") (pinfunction "61_61") (pintype "bidirectional"))
      (node (ref "X-SOUTH") (pin "62") (pinfunction "62_62") (pintype "bidirectional"))
    )
    (net (code "90") (name "OUT22_N") (class "Default")
      (node (ref "X-SOUTH") (pin "59") (pinfunction "59_59") (pintype "bidirectional"))
    )
    (net (code "91") (name "OUT22_P") (class "Default")
      (node (ref "X-SOUTH") (pin "57") (pinfunction "57_57") (pintype "bidirectional"))
    )
    (net (code "92") (name "OUT23_N") (class "Default")
      (node (ref "X-EAST") (pin "66") (pinfunction "66_66") (pintype "bidirectional"))
      (node (ref "X-SOUTH") (pin "53") (pinfunction "53_53") (pintype "bidirectional"))
    )
    (net (code "93") (name "OUT23_P") (class "Default")
      (node (ref "X-EAST") (pin "68") (pinfunction "68_68") (pintype "bidirectional"))
      (node (ref "X-SOUTH") (pin "51") (pinfunction "51_51") (pintype "bidirectional"))
    )
    (net (code "94") (name "OUT24_N") (class "Default")
      (node (ref "X-SOUTH") (pin "52") (pinfunction "52_52") (pintype "bidirectional"))
    )
    (net (code "95") (name "OUT24_P") (class "Default")
      (node (ref "X-SOUTH") (pin "50") (pinfunction "50_50") (pintype "bidirectional"))
    )
    (net (code "96") (name "OUT25_N") (class "Default")
      (node (ref "X-EAST") (pin "65") (pinfunction "65_65") (pintype "bidirectional"))
      (node (ref "X-SOUTH") (pin "58") (pinfunction "58_58") (pintype "bidirectional"))
    )
    (net (code "97") (name "OUT25_P") (class "Default")
      (node (ref "X-EAST") (pin "67") (pinfunction "67_67") (pintype "bidirectional"))
      (node (ref "X-SOUTH") (pin "56") (pinfunction "56_56") (pintype "bidirectional"))
    )
    (net (code "98") (name "OUT26_N") (class "Default")
      (node (ref "X-SOUTH") (pin "47") (pinfunction "47_47") (pintype "bidirectional"))
    )
    (net (code "99") (name "OUT26_P") (class "Default")
      (node (ref "X-SOUTH") (pin "45") (pinfunction "45_45") (pintype "bidirectional"))
    )
    (net (code "100") (name "OUT27_N") (class "Default")
      (node (ref "X-EAST") (pin "73") (pinfunction "73_73") (pintype "bidirectional"))
      (node (ref "X-SOUTH") (pin "40") (pinfunction "40_40") (pintype "bidirectional"))
    )
    (net (code "101") (name "OUT27_P") (class "Default")
      (node (ref "X-EAST") (pin "75") (pinfunction "75_75") (pintype "bidirectional"))
      (node (ref "X-SOUTH") (pin "38") (pinfunction "38_38") (pintype "bidirectional"))
    )
    (net (code "102") (name "OUT28_N") (class "Default")
      (node (ref "X-SOUTH") (pin "46") (pinfunction "46_46") (pintype "bidirectional"))
    )
    (net (code "103") (name "OUT28_P") (class "Default")
      (node (ref "X-SOUTH") (pin "44") (pinfunction "44_44") (pintype "bidirectional"))
    )
    (net (code "104") (name "OUT29_N") (class "Default")
      (node (ref "X-EAST") (pin "72") (pinfunction "72_72") (pintype "bidirectional"))
      (node (ref "X-SOUTH") (pin "41") (pinfunction "41_41") (pintype "bidirectional"))
    )
    (net (code "105") (name "OUT29_P") (class "Default")
      (node (ref "X-EAST") (pin "74") (pinfunction "74_74") (pintype "bidirectional"))
      (node (ref "X-SOUTH") (pin "39") (pinfunction "39_39") (pintype "bidirectional"))
    )
    (net (code "106") (name "OUT30_N") (class "Default")
      (node (ref "X-SOUTH") (pin "34") (pinfunction "34_34") (pintype "bidirectional"))
    )
    (net (code "107") (name "OUT30_P") (class "Default")
      (node (ref "X-SOUTH") (pin "32") (pinfunction "32_32") (pintype "bidirectional"))
    )
    (net (code "108") (name "OUT31_N") (class "Default")
      (node (ref "X-EAST") (pin "78") (pinfunction "78_78") (pintype "bidirectional"))
      (node (ref "X-SOUTH") (pin "35") (pinfunction "35_35") (pintype "bidirectional"))
    )
    (net (code "109") (name "OUT31_P") (class "Default")
      (node (ref "X-EAST") (pin "80") (pinfunction "80_80") (pintype "bidirectional"))
      (node (ref "X-SOUTH") (pin "33") (pinfunction "33_33") (pintype "bidirectional"))
    )
    (net (code "110") (name "OUT32_N") (class "Default")
      (node (ref "X-SOUTH") (pin "28") (pinfunction "28_28") (pintype "bidirectional"))
    )
    (net (code "111") (name "OUT32_P") (class "Default")
      (node (ref "X-SOUTH") (pin "26") (pinfunction "26_26") (pintype "bidirectional"))
    )
    (net (code "112") (name "OUT33_N") (class "Default")
      (node (ref "X-NORTH") (pin "20") (pinfunction "20_20") (pintype "bidirectional"))
      (node (ref "X-WEST") (pin "67") (pinfunction "67_67") (pintype "bidirectional"))
    )
    (net (code "113") (name "OUT33_P") (class "Default")
      (node (ref "X-NORTH") (pin "22") (pinfunction "22_22") (pintype "bidirectional"))
      (node (ref "X-WEST") (pin "65") (pinfunction "65_65") (pintype "bidirectional"))
    )
    (net (code "114") (name "OUT34_N") (class "Default")
      (node (ref "X-NORTH") (pin "27") (pinfunction "27_27") (pintype "bidirectional"))
    )
    (net (code "115") (name "OUT34_P") (class "Default")
      (node (ref "X-NORTH") (pin "29") (pinfunction "29_29") (pintype "bidirectional"))
    )
    (net (code "116") (name "OUT35_N") (class "Default")
      (node (ref "X-NORTH") (pin "26") (pinfunction "26_26") (pintype "bidirectional"))
      (node (ref "X-WEST") (pin "61") (pinfunction "61_61") (pintype "bidirectional"))
    )
    (net (code "117") (name "OUT35_P") (class "Default")
      (node (ref "X-NORTH") (pin "28") (pinfunction "28_28") (pintype "bidirectional"))
      (node (ref "X-WEST") (pin "59") (pinfunction "59_59") (pintype "bidirectional"))
    )
    (net (code "118") (name "OUT36_N") (class "Default")
      (node (ref "X-NORTH") (pin "33") (pinfunction "33_33") (pintype "bidirectional"))
    )
    (net (code "119") (name "OUT36_P") (class "Default")
      (node (ref "X-NORTH") (pin "35") (pinfunction "35_35") (pintype "bidirectional"))
    )
    (net (code "120") (name "OUT37_N") (class "Default")
      (node (ref "X-NORTH") (pin "32") (pinfunction "32_32") (pintype "bidirectional"))
      (node (ref "X-WEST") (pin "47") (pinfunction "47_47") (pintype "bidirectional"))
    )
    (net (code "121") (name "OUT37_P") (class "Default")
      (node (ref "X-NORTH") (pin "34") (pinfunction "34_34") (pintype "bidirectional"))
      (node (ref "X-WEST") (pin "45") (pinfunction "45_45") (pintype "bidirectional"))
    )
    (net (code "122") (name "OUT38_N") (class "Default")
      (node (ref "X-NORTH") (pin "38") (pinfunction "38_38") (pintype "bidirectional"))
    )
    (net (code "123") (name "OUT38_P") (class "Default")
      (node (ref "X-NORTH") (pin "40") (pinfunction "40_40") (pintype "bidirectional"))
    )
    (net (code "124") (name "OUT39_N") (class "Default")
      (node (ref "X-NORTH") (pin "39") (pinfunction "39_39") (pintype "bidirectional"))
      (node (ref "X-WEST") (pin "80") (pinfunction "80_80") (pintype "bidirectional"))
    )
    (net (code "125") (name "OUT39_P") (class "Default")
      (node (ref "X-NORTH") (pin "41") (pinfunction "41_41") (pintype "bidirectional"))
      (node (ref "X-WEST") (pin "78") (pinfunction "78_78") (pintype "bidirectional"))
    )
    (net (code "126") (name "OUT40_N") (class "Default")
      (node (ref "X-NORTH") (pin "44") (pinfunction "44_44") (pintype "bidirectional"))
    )
    (net (code "127") (name "OUT40_P") (class "Default")
      (node (ref "X-NORTH") (pin "46") (pinfunction "46_46") (pintype "bidirectional"))
    )
    (net (code "128") (name "OUT41_N") (class "Default")
      (node (ref "X-NORTH") (pin "45") (pinfunction "45_45") (pintype "bidirectional"))
      (node (ref "X-WEST") (pin "74") (pinfunction "74_74") (pintype "bidirectional"))
    )
    (net (code "129") (name "OUT41_P") (class "Default")
      (node (ref "X-NORTH") (pin "47") (pinfunction "47_47") (pintype "bidirectional"))
      (node (ref "X-WEST") (pin "72") (pinfunction "72_72") (pintype "bidirectional"))
    )
    (net (code "130") (name "OUT42_N") (class "Default")
      (node (ref "X-NORTH") (pin "50") (pinfunction "50_50") (pintype "bidirectional"))
    )
    (net (code "131") (name "OUT42_P") (class "Default")
      (node (ref "X-NORTH") (pin "52") (pinfunction "52_52") (pintype "bidirectional"))
    )
    (net (code "132") (name "OUT43_N") (class "Default")
      (node (ref "X-NORTH") (pin "51") (pinfunction "51_51") (pintype "bidirectional"))
      (node (ref "X-WEST") (pin "68") (pinfunction "68_68") (pintype "bidirectional"))
    )
    (net (code "133") (name "OUT43_P") (class "Default")
      (node (ref "X-NORTH") (pin "53") (pinfunction "53_53") (pintype "bidirectional"))
      (node (ref "X-WEST") (pin "66") (pinfunction "66_66") (pintype "bidirectional"))
    )
    (net (code "134") (name "OUT44_N") (class "Default")
      (node (ref "X-NORTH") (pin "56") (pinfunction "56_56") (pintype "bidirectional"))
    )
    (net (code "135") (name "OUT44_P") (class "Default")
      (node (ref "X-NORTH") (pin "58") (pinfunction "58_58") (pintype "bidirectional"))
    )
    (net (code "136") (name "OUT45_N") (class "Default")
      (node (ref "X-NORTH") (pin "57") (pinfunction "57_57") (pintype "bidirectional"))
      (node (ref "X-WEST") (pin "62") (pinfunction "62_62") (pintype "bidirectional"))
    )
    (net (code "137") (name "OUT45_P") (class "Default")
      (node (ref "X-NORTH") (pin "59") (pinfunction "59_59") (pintype "bidirectional"))
      (node (ref "X-WEST") (pin "60") (pinfunction "60_60") (pintype "bidirectional"))
    )
    (net (code "138") (name "OUT46_N") (class "Default")
      (node (ref "X-NORTH") (pin "62") (pinfunction "62_62") (pintype "bidirectional"))
    )
    (net (code "139") (name "OUT46_P") (class "Default")
      (node (ref "X-NORTH") (pin "64") (pinfunction "64_64") (pintype "bidirectional"))
    )
    (net (code "140") (name "OUT47_N") (class "Default")
      (node (ref "X-NORTH") (pin "63") (pinfunction "63_63") (pintype "bidirectional"))
      (node (ref "X-WEST") (pin "56") (pinfunction "56_56") (pintype "bidirectional"))
    )
    (net (code "141") (name "OUT47_P") (class "Default")
      (node (ref "X-NORTH") (pin "65") (pinfunction "65_65") (pintype "bidirectional"))
      (node (ref "X-WEST") (pin "54") (pinfunction "54_54") (pintype "bidirectional"))
    )
    (net (code "142") (name "OUT48_N") (class "Default")
      (node (ref "X-NORTH") (pin "68") (pinfunction "68_68") (pintype "bidirectional"))
    )
    (net (code "143") (name "OUT48_P") (class "Default")
      (node (ref "X-NORTH") (pin "70") (pinfunction "70_70") (pintype "bidirectional"))
    )
    (net (code "144") (name "OUT49_N") (class "Default")
      (node (ref "X-EAST") (pin "48") (pinfunction "48_48") (pintype "bidirectional"))
      (node (ref "X-NORTH") (pin "74") (pinfunction "74_74") (pintype "bidirectional"))
    )
    (net (code "145") (name "OUT49_P") (class "Default")
      (node (ref "X-EAST") (pin "46") (pinfunction "46_46") (pintype "bidirectional"))
      (node (ref "X-NORTH") (pin "76") (pinfunction "76_76") (pintype "bidirectional"))
    )
    (net (code "146") (name "OUT50_N") (class "Default")
      (node (ref "X-NORTH") (pin "69") (pinfunction "69_69") (pintype "bidirectional"))
    )
    (net (code "147") (name "OUT50_P") (class "Default")
      (node (ref "X-NORTH") (pin "71") (pinfunction "71_71") (pintype "bidirectional"))
    )
    (net (code "148") (name "OUT51_N") (class "Default")
      (node (ref "X-EAST") (pin "42") (pinfunction "42_42") (pintype "bidirectional"))
      (node (ref "X-NORTH") (pin "80") (pinfunction "80_80") (pintype "bidirectional"))
    )
    (net (code "149") (name "OUT51_P") (class "Default")
      (node (ref "X-EAST") (pin "40") (pinfunction "40_40") (pintype "bidirectional"))
      (node (ref "X-NORTH") (pin "82") (pinfunction "82_82") (pintype "bidirectional"))
    )
    (net (code "150") (name "OUT52_N") (class "Default")
      (node (ref "X-NORTH") (pin "75") (pinfunction "75_75") (pintype "bidirectional"))
    )
    (net (code "151") (name "OUT52_P") (class "Default")
      (node (ref "X-NORTH") (pin "77") (pinfunction "77_77") (pintype "bidirectional"))
    )
    (net (code "152") (name "OUT53_N") (class "Default")
      (node (ref "X-EAST") (pin "47") (pinfunction "47_47") (pintype "bidirectional"))
      (node (ref "X-NORTH") (pin "86") (pinfunction "86_86") (pintype "bidirectional"))
    )
    (net (code "153") (name "OUT53_P") (class "Default")
      (node (ref "X-EAST") (pin "45") (pinfunction "45_45") (pintype "bidirectional"))
      (node (ref "X-NORTH") (pin "88") (pinfunction "88_88") (pintype "bidirectional"))
    )
    (net (code "154") (name "OUT54_N") (class "Default")
      (node (ref "X-NORTH") (pin "81") (pinfunction "81_81") (pintype "bidirectional"))
    )
    (net (code "155") (name "OUT54_P") (class "Default")
      (node (ref "X-NORTH") (pin "83") (pinfunction "83_83") (pintype "bidirectional"))
    )
    (net (code "156") (name "OUT55_N") (class "Default")
      (node (ref "X-EAST") (pin "41") (pinfunction "41_41") (pintype "bidirectional"))
      (node (ref "X-NORTH") (pin "92") (pinfunction "92_92") (pintype "bidirectional"))
    )
    (net (code "157") (name "OUT55_P") (class "Default")
      (node (ref "X-EAST") (pin "39") (pinfunction "39_39") (pintype "bidirectional"))
      (node (ref "X-NORTH") (pin "94") (pinfunction "94_94") (pintype "bidirectional"))
    )
    (net (code "158") (name "OUT56_N") (class "Default")
      (node (ref "X-NORTH") (pin "87") (pinfunction "87_87") (pintype "bidirectional"))
    )
    (net (code "159") (name "OUT56_P") (class "Default")
      (node (ref "X-NORTH") (pin "89") (pinfunction "89_89") (pintype "bidirectional"))
    )
    (net (code "160") (name "OUT57_N") (class "Default")
      (node (ref "X-EAST") (pin "35") (pinfunction "35_35") (pintype "bidirectional"))
      (node (ref "X-NORTH") (pin "98") (pinfunction "98_98") (pintype "bidirectional"))
    )
    (net (code "161") (name "OUT57_P") (class "Default")
      (node (ref "X-EAST") (pin "33") (pinfunction "33_33") (pintype "bidirectional"))
      (node (ref "X-NORTH") (pin "100") (pinfunction "100_100") (pintype "bidirectional"))
    )
    (net (code "162") (name "OUT58_N") (class "Default")
      (node (ref "X-NORTH") (pin "93") (pinfunction "93_93") (pintype "bidirectional"))
    )
    (net (code "163") (name "OUT58_P") (class "Default")
      (node (ref "X-NORTH") (pin "95") (pinfunction "95_95") (pintype "bidirectional"))
    )
    (net (code "164") (name "OUT59_N") (class "Default")
      (node (ref "X-EAST") (pin "27") (pinfunction "27_27") (pintype "bidirectional"))
      (node (ref "X-NORTH") (pin "104") (pinfunction "104_104") (pintype "bidirectional"))
    )
    (net (code "165") (name "OUT59_P") (class "Default")
      (node (ref "X-EAST") (pin "25") (pinfunction "25_25") (pintype "bidirectional"))
      (node (ref "X-NORTH") (pin "106") (pinfunction "106_106") (pintype "bidirectional"))
    )
    (net (code "166") (name "OUT60_N") (class "Default")
      (node (ref "X-NORTH") (pin "110") (pinfunction "110_110") (pintype "bidirectional"))
    )
    (net (code "167") (name "OUT60_P") (class "Default")
      (node (ref "X-NORTH") (pin "112") (pinfunction "112_112") (pintype "bidirectional"))
    )
    (net (code "168") (name "OUT61_N") (class "Default")
      (node (ref "X-EAST") (pin "36") (pinfunction "36_36") (pintype "bidirectional"))
      (node (ref "X-NORTH") (pin "99") (pinfunction "99_99") (pintype "bidirectional"))
    )
    (net (code "169") (name "OUT61_P") (class "Default")
      (node (ref "X-EAST") (pin "34") (pinfunction "34_34") (pintype "bidirectional"))
      (node (ref "X-NORTH") (pin "101") (pinfunction "101_101") (pintype "bidirectional"))
    )
    (net (code "170") (name "OUT62_N") (class "Default")
      (node (ref "X-NORTH") (pin "116") (pinfunction "116_116") (pintype "bidirectional"))
    )
    (net (code "171") (name "OUT62_P") (class "Default")
      (node (ref "X-NORTH") (pin "118") (pinfunction "118_118") (pintype "bidirectional"))
    )
    (net (code "172") (name "OUT63_N") (class "Default")
      (node (ref "X-EAST") (pin "30") (pinfunction "30_30") (pintype "bidirectional"))
      (node (ref "X-NORTH") (pin "105") (pinfunction "105_105") (pintype "bidirectional"))
    )
    (net (code "173") (name "OUT63_P") (class "Default")
      (node (ref "X-EAST") (pin "28") (pinfunction "28_28") (pintype "bidirectional"))
      (node (ref "X-NORTH") (pin "107") (pinfunction "107_107") (pintype "bidirectional"))
    )
    (net (code "174") (name "OUT64_N") (class "Default")
      (node (ref "X-NORTH") (pin "111") (pinfunction "111_111") (pintype "bidirectional"))
    )
    (net (code "175") (name "OUT64_P") (class "Default")
      (node (ref "X-NORTH") (pin "113") (pinfunction "113_113") (pintype "bidirectional"))
    )
    (net (code "176") (name "OUTCLK_N") (class "Default")
      (node (ref "X-NORTH") (pin "15") (pinfunction "15_15") (pintype "bidirectional"))
      (node (ref "X-WEST") (pin "53") (pinfunction "53_53") (pintype "bidirectional"))
    )
    (net (code "177") (name "OUTCLK_P") (class "Default")
      (node (ref "X-NORTH") (pin "17") (pinfunction "17_17") (pintype "bidirectional"))
      (node (ref "X-WEST") (pin "55") (pinfunction "55_55") (pintype "bidirectional"))
    )
    (net (code "178") (name "OUTCTR_N") (class "Default")
      (node (ref "X-SOUTH") (pin "125") (pinfunction "125_125") (pintype "bidirectional"))
      (node (ref "X-WEST") (pin "22") (pinfunction "22_22") (pintype "bidirectional"))
    )
    (net (code "179") (name "OUTCTR_P") (class "Default")
      (node (ref "X-SOUTH") (pin "123") (pinfunction "123_123") (pintype "bidirectional"))
      (node (ref "X-WEST") (pin "24") (pinfunction "24_24") (pintype "bidirectional"))
    )
    (net (code "180") (name "RES1") (class "Default")
      (node (ref "X-WEST") (pin "79") (pinfunction "79_79") (pintype "bidirectional"))
    )
    (net (code "181") (name "RES2") (class "Default")
      (node (ref "X-WEST") (pin "81") (pinfunction "81_81") (pintype "bidirectional"))
    )
    (net (code "182") (name "RES3") (class "Default")
      (node (ref "X-WEST") (pin "83") (pinfunction "83_83") (pintype "bidirectional"))
    )
    (net (code "183") (name "RES4") (class "Default")
      (node (ref "X-EAST") (pin "79") (pinfunction "79_79") (pintype "bidirectional"))
    )
    (net (code "184") (name "RES5") (class "Default")
      (node (ref "X-EAST") (pin "81") (pinfunction "81_81") (pintype "bidirectional"))
    )
    (net (code "185") (name "RES6") (class "Default")
      (node (ref "X-EAST") (pin "83") (pinfunction "83_83") (pintype "bidirectional"))
    )
    (net (code "186") (name "S00_N") (class "Default")
      (node (ref "X-SOUTH") (pin "16") (pinfunction "16_16") (pintype "bidirectional"))
    )
    (net (code "187") (name "S00_P") (class "Default")
      (node (ref "X-SOUTH") (pin "14") (pinfunction "14_14") (pintype "bidirectional"))
    )
    (net (code "188") (name "S01_N") (class "Default")
      (node (ref "X-SOUTH") (pin "17") (pinfunction "17_17") (pintype "bidirectional"))
    )
    (net (code "189") (name "S01_P") (class "Default")
      (node (ref "X-SOUTH") (pin "15") (pinfunction "15_15") (pintype "bidirectional"))
    )
    (net (code "190") (name "S02_N") (class "Default")
      (node (ref "X-SOUTH") (pin "22") (pinfunction "22_22") (pintype "bidirectional"))
    )
    (net (code "191") (name "S02_P") (class "Default")
      (node (ref "X-SOUTH") (pin "20") (pinfunction "20_20") (pintype "bidirectional"))
    )
    (net (code "192") (name "S03_N") (class "Default")
      (node (ref "X-SOUTH") (pin "23") (pinfunction "23_23") (pintype "bidirectional"))
    )
    (net (code "193") (name "S03_P") (class "Default")
      (node (ref "X-SOUTH") (pin "21") (pinfunction "21_21") (pintype "bidirectional"))
    )
    (net (code "194") (name "S05_N") (class "Default")
      (node (ref "X-SOUTH") (pin "29") (pinfunction "29_29") (pintype "bidirectional"))
    )
    (net (code "195") (name "S05_P") (class "Default")
      (node (ref "X-SOUTH") (pin "27") (pinfunction "27_27") (pintype "bidirectional"))
    )
    (net (code "196") (name "S38_N") (class "Default")
      (node (ref "X-SOUTH") (pin "130") (pinfunction "130_130") (pintype "bidirectional"))
    )
    (net (code "197") (name "S38_P") (class "Default")
      (node (ref "X-SOUTH") (pin "128") (pinfunction "128_128") (pintype "bidirectional"))
    )
    (net (code "198") (name "S39_N") (class "Default")
      (node (ref "X-SOUTH") (pin "131") (pinfunction "131_131") (pintype "bidirectional"))
    )
    (net (code "199") (name "S39_P") (class "Default")
      (node (ref "X-SOUTH") (pin "129") (pinfunction "129_129") (pintype "bidirectional"))
    )
    (net (code "200") (name "SYS_RES_N") (class "Default")
      (node (ref "X-EAST") (pin "22") (pinfunction "22_22") (pintype "bidirectional"))
      (node (ref "X-NORTH") (pin "125") (pinfunction "125_125") (pintype "bidirectional"))
    )
    (net (code "201") (name "S_CHK_EN") (class "Default")
      (node (ref "X-EAST") (pin "94") (pinfunction "94_94") (pintype "bidirectional"))
      (node (ref "X-SOUTH") (pin "8") (pinfunction "8_8") (pintype "bidirectional"))
    )
    (net (code "202") (name "S_CHK_V") (class "Default")
      (node (ref "X-EAST") (pin "92") (pinfunction "92_92") (pintype "bidirectional"))
      (node (ref "X-SOUTH") (pin "10") (pinfunction "10_10") (pintype "bidirectional"))
    )
    (net (code "203") (name "S_I2C_EN") (class "Default")
      (node (ref "X-SOUTH") (pin "137") (pinfunction "137_137") (pintype "bidirectional"))
      (node (ref "X-WEST") (pin "7") (pinfunction "7_7") (pintype "bidirectional"))
    )
    (net (code "204") (name "S_I2C_V") (class "Default")
      (node (ref "X-SOUTH") (pin "135") (pinfunction "135_135") (pintype "bidirectional"))
      (node (ref "X-WEST") (pin "9") (pinfunction "9_9") (pintype "bidirectional"))
    )
    (net (code "205") (name "S_SCK") (class "Default")
      (node (ref "X-SOUTH") (pin "144") (pinfunction "144_144") (pintype "bidirectional"))
      (node (ref "X-WEST") (pin "2") (pinfunction "2_2") (pintype "bidirectional"))
    )
    (net (code "206") (name "S_SCL") (class "Default")
      (node (ref "X-SOUTH") (pin "143") (pinfunction "143_143") (pintype "bidirectional"))
      (node (ref "X-WEST") (pin "1") (pinfunction "1_1") (pintype "bidirectional"))
    )
    (net (code "207") (name "S_SDA") (class "Default")
      (node (ref "X-SOUTH") (pin "141") (pinfunction "141_141") (pintype "bidirectional"))
      (node (ref "X-WEST") (pin "3") (pinfunction "3_3") (pintype "bidirectional"))
    )
    (net (code "208") (name "S_SDI") (class "Default")
      (node (ref "X-SOUTH") (pin "140") (pinfunction "140_140") (pintype "bidirectional"))
      (node (ref "X-WEST") (pin "6") (pinfunction "6_6") (pintype "bidirectional"))
    )
    (net (code "209") (name "S_SDO") (class "Default")
      (node (ref "X-SOUTH") (pin "142") (pinfunction "142_142") (pintype "bidirectional"))
      (node (ref "X-WEST") (pin "4") (pinfunction "4_4") (pintype "bidirectional"))
    )
    (net (code "210") (name "S_SPI_EN") (class "Default")
      (node (ref "X-SOUTH") (pin "136") (pinfunction "136_136") (pintype "bidirectional"))
      (node (ref "X-WEST") (pin "8") (pinfunction "8_8") (pintype "bidirectional"))
    )
    (net (code "211") (name "S_SPI_V") (class "Default")
      (node (ref "X-SOUTH") (pin "134") (pinfunction "134_134") (pintype "bidirectional"))
      (node (ref "X-WEST") (pin "10") (pinfunction "10_10") (pintype "bidirectional"))
    )
    (net (code "212") (name "S_VE") (class "Default")
      (node (ref "C7") (pin "1") (pinfunction "1_1") (pintype "passive"))
      (node (ref "SE") (pin "1") (pinfunction "1_1") (pintype "passive"))
      (node (ref "X-SOUTH") (pin "13") (pinfunction "13_13") (pintype "bidirectional"))
      (node (ref "X-SOUTH") (pin "19") (pinfunction "19_19") (pintype "bidirectional"))
      (node (ref "X-SOUTH") (pin "31") (pinfunction "31_31") (pintype "bidirectional"))
      (node (ref "X-SOUTH") (pin "37") (pinfunction "37_37") (pintype "bidirectional"))
    )
    (net (code "213") (name "S_VE_CV") (class "Default")
      (node (ref "X-EAST") (pin "100") (pinfunction "100_100") (pintype "bidirectional"))
      (node (ref "X-SOUTH") (pin "2") (pinfunction "2_2") (pintype "bidirectional"))
    )
    (net (code "214") (name "S_VE_OV") (class "Default")
      (node (ref "X-EAST") (pin "99") (pinfunction "99_99") (pintype "bidirectional"))
      (node (ref "X-SOUTH") (pin "1") (pinfunction "1_1") (pintype "bidirectional"))
    )
    (net (code "215") (name "S_VE_RS") (class "Default")
      (node (ref "X-EAST") (pin "84") (pinfunction "84_84") (pintype "bidirectional"))
      (node (ref "X-SOUTH") (pin "25") (pinfunction "25_25") (pintype "bidirectional"))
    )
    (net (code "216") (name "S_VE_UV") (class "Default")
      (node (ref "X-EAST") (pin "89") (pinfunction "89_89") (pintype "bidirectional"))
      (node (ref "X-SOUTH") (pin "7") (pinfunction "7_7") (pintype "bidirectional"))
    )
    (net (code "217") (name "S_VS") (class "Default")
      (node (ref "C6") (pin "1") (pinfunction "1_1") (pintype "passive"))
      (node (ref "SW") (pin "1") (pinfunction "1_1") (pintype "passive"))
      (node (ref "X-SOUTH") (pin "49") (pinfunction "49_49") (pintype "bidirectional"))
      (node (ref "X-SOUTH") (pin "55") (pinfunction "55_55") (pintype "bidirectional"))
      (node (ref "X-SOUTH") (pin "61") (pinfunction "61_61") (pintype "bidirectional"))
      (node (ref "X-SOUTH") (pin "67") (pinfunction "67_67") (pintype "bidirectional"))
      (node (ref "X-SOUTH") (pin "79") (pinfunction "79_79") (pintype "bidirectional"))
      (node (ref "X-SOUTH") (pin "85") (pinfunction "85_85") (pintype "bidirectional"))
      (node (ref "X-SOUTH") (pin "91") (pinfunction "91_91") (pintype "bidirectional"))
      (node (ref "X-SOUTH") (pin "97") (pinfunction "97_97") (pintype "bidirectional"))
    )
    (net (code "218") (name "S_VS_CV") (class "Default")
      (node (ref "X-EAST") (pin "98") (pinfunction "98_98") (pintype "bidirectional"))
      (node (ref "X-SOUTH") (pin "4") (pinfunction "4_4") (pintype "bidirectional"))
    )
    (net (code "219") (name "S_VS_OV") (class "Default")
      (node (ref "X-EAST") (pin "97") (pinfunction "97_97") (pintype "bidirectional"))
      (node (ref "X-SOUTH") (pin "3") (pinfunction "3_3") (pintype "bidirectional"))
    )
    (net (code "220") (name "S_VS_RS") (class "Default")
      (node (ref "X-EAST") (pin "86") (pinfunction "86_86") (pintype "bidirectional"))
      (node (ref "X-SOUTH") (pin "73") (pinfunction "73_73") (pintype "bidirectional"))
    )
    (net (code "221") (name "S_VS_UV") (class "Default")
      (node (ref "X-EAST") (pin "87") (pinfunction "87_87") (pintype "bidirectional"))
      (node (ref "X-SOUTH") (pin "9") (pinfunction "9_9") (pintype "bidirectional"))
    )
    (net (code "222") (name "S_VW") (class "Default")
      (node (ref "C2") (pin "1") (pinfunction "1_1") (pintype "passive"))
      (node (ref "SW") (pin "2") (pinfunction "2_2") (pintype "passive"))
      (node (ref "X-SOUTH") (pin "109") (pinfunction "109_109") (pintype "bidirectional"))
      (node (ref "X-SOUTH") (pin "115") (pinfunction "115_115") (pintype "bidirectional"))
      (node (ref "X-SOUTH") (pin "127") (pinfunction "127_127") (pintype "bidirectional"))
      (node (ref "X-SOUTH") (pin "133") (pinfunction "133_133") (pintype "bidirectional"))
    )
    (net (code "223") (name "S_VW_CV") (class "Default")
      (node (ref "X-EAST") (pin "96") (pinfunction "96_96") (pintype "bidirectional"))
      (node (ref "X-SOUTH") (pin "6") (pinfunction "6_6") (pintype "bidirectional"))
    )
    (net (code "224") (name "S_VW_OV") (class "Default")
      (node (ref "X-EAST") (pin "95") (pinfunction "95_95") (pintype "bidirectional"))
      (node (ref "X-SOUTH") (pin "5") (pinfunction "5_5") (pintype "bidirectional"))
    )
    (net (code "225") (name "S_VW_RS") (class "Default")
      (node (ref "X-EAST") (pin "88") (pinfunction "88_88") (pintype "bidirectional"))
      (node (ref "X-SOUTH") (pin "121") (pinfunction "121_121") (pintype "bidirectional"))
    )
    (net (code "226") (name "S_VW_UV") (class "Default")
      (node (ref "X-EAST") (pin "85") (pinfunction "85_85") (pintype "bidirectional"))
      (node (ref "X-SOUTH") (pin "11") (pinfunction "11_11") (pintype "bidirectional"))
    )
    (net (code "227") (name "TCK") (class "Default")
      (node (ref "X-WEST") (pin "12") (pinfunction "12_12") (pintype "bidirectional"))
    )
    (net (code "228") (name "TDI") (class "Default")
      (node (ref "X-WEST") (pin "16") (pinfunction "16_16") (pintype "bidirectional"))
    )
    (net (code "229") (name "TDIG1") (class "Default")
      (node (ref "X-EAST") (pin "18") (pinfunction "18_18") (pintype "bidirectional"))
      (node (ref "X-NORTH") (pin "123") (pinfunction "123_123") (pintype "bidirectional"))
    )
    (net (code "230") (name "TDIG2") (class "Default")
      (node (ref "X-NORTH") (pin "130") (pinfunction "130_130") (pintype "bidirectional"))
    )
    (net (code "231") (name "TDO") (class "Default")
      (node (ref "X-WEST") (pin "18") (pinfunction "18_18") (pintype "bidirectional"))
    )
    (net (code "232") (name "TMS") (class "Default")
      (node (ref "X-WEST") (pin "14") (pinfunction "14_14") (pintype "bidirectional"))
    )
    (net (code "233") (name "TP9") (class "Default")
      (node (ref "X-NORTH") (pin "119") (pinfunction "119_119") (pintype "bidirectional"))
    )
    (net (code "234") (name "T_EXP1") (class "Default")
      (node (ref "X-EAST") (pin "12") (pinfunction "12_12") (pintype "bidirectional"))
      (node (ref "X-NORTH") (pin "131") (pinfunction "131_131") (pintype "bidirectional"))
    )
    (net (code "235") (name "T_EXP2") (class "Default")
      (node (ref "X-EAST") (pin "16") (pinfunction "16_16") (pintype "bidirectional"))
      (node (ref "X-NORTH") (pin "117") (pinfunction "117_117") (pintype "bidirectional"))
    )
    (net (code "236") (name "W_EN") (class "Default")
      (node (ref "X-WEST") (pin "19") (pinfunction "19_19") (pintype "bidirectional"))
    )
    (net (code "237") (name "W_I2C_EN") (class "Default")
      (node (ref "X-WEST") (pin "13") (pinfunction "13_13") (pintype "bidirectional"))
    )
    (net (code "238") (name "W_I2C_V") (class "Default")
      (node (ref "X-WEST") (pin "11") (pinfunction "11_11") (pintype "bidirectional"))
    )
    (net (code "239") (name "W_SCL") (class "Default")
      (node (ref "X-WEST") (pin "15") (pinfunction "15_15") (pintype "bidirectional"))
    )
    (net (code "240") (name "W_SDA") (class "Default")
      (node (ref "X-WEST") (pin "17") (pinfunction "17_17") (pintype "bidirectional"))
    )
    (net (code "241") (name "W_VW") (class "Default")
      (node (ref "C8") (pin "1") (pinfunction "1_1") (pintype "passive"))
      (node (ref "NW") (pin "2") (pinfunction "2_2") (pintype "passive"))
    )
    (net (code "242") (name "W_VW_CV") (class "Default")
      (node (ref "X-WEST") (pin "90") (pinfunction "90_90") (pintype "bidirectional"))
    )
    (net (code "243") (name "W_VW_OV") (class "Default")
      (node (ref "X-WEST") (pin "93") (pinfunction "93_93") (pintype "bidirectional"))
    )
    (net (code "244") (name "W_VW_UV") (class "Default")
      (node (ref "X-WEST") (pin "91") (pinfunction "91_91") (pintype "bidirectional"))
    )
    (net (code "245") (name "unconnected-(X-EAST-PadM1)") (class "Default")
      (node (ref "X-EAST") (pin "M1") (pinfunction "M1_M1") (pintype "bidirectional"))
    )
    (net (code "246") (name "unconnected-(X-EAST-PadM2)") (class "Default")
      (node (ref "X-EAST") (pin "M2") (pinfunction "M2_M2") (pintype "bidirectional"))
    )
    (net (code "247") (name "unconnected-(X-NORTH-PadM1)") (class "Default")
      (node (ref "X-NORTH") (pin "M1") (pinfunction "M1_M1") (pintype "bidirectional"))
    )
    (net (code "248") (name "unconnected-(X-NORTH-PadM2)") (class "Default")
      (node (ref "X-NORTH") (pin "M2") (pinfunction "M2_M2") (pintype "bidirectional"))
    )
    (net (code "249") (name "unconnected-(X-SOUTH-PadM1)") (class "Default")
      (node (ref "X-SOUTH") (pin "M1") (pinfunction "M1_M1") (pintype "bidirectional"))
    )
    (net (code "250") (name "unconnected-(X-SOUTH-PadM2)") (class "Default")
      (node (ref "X-SOUTH") (pin "M2") (pinfunction "M2_M2") (pintype "bidirectional"))
    )
    (net (code "251") (name "unconnected-(X-WEST-PadM1)") (class "Default")
      (node (ref "X-WEST") (pin "M1") (pinfunction "M1_M1") (pintype "bidirectional"))
    )
    (net (code "252") (name "unconnected-(X-WEST-PadM2)") (class "Default")
      (node (ref "X-WEST") (pin "M2") (pinfunction "M2_M2") (pintype "bidirectional"))
    )
  )
)
